# DATALOGGER_CA_ADC_V1.net
KiCad netlist of a schematic drawn in EAGLE
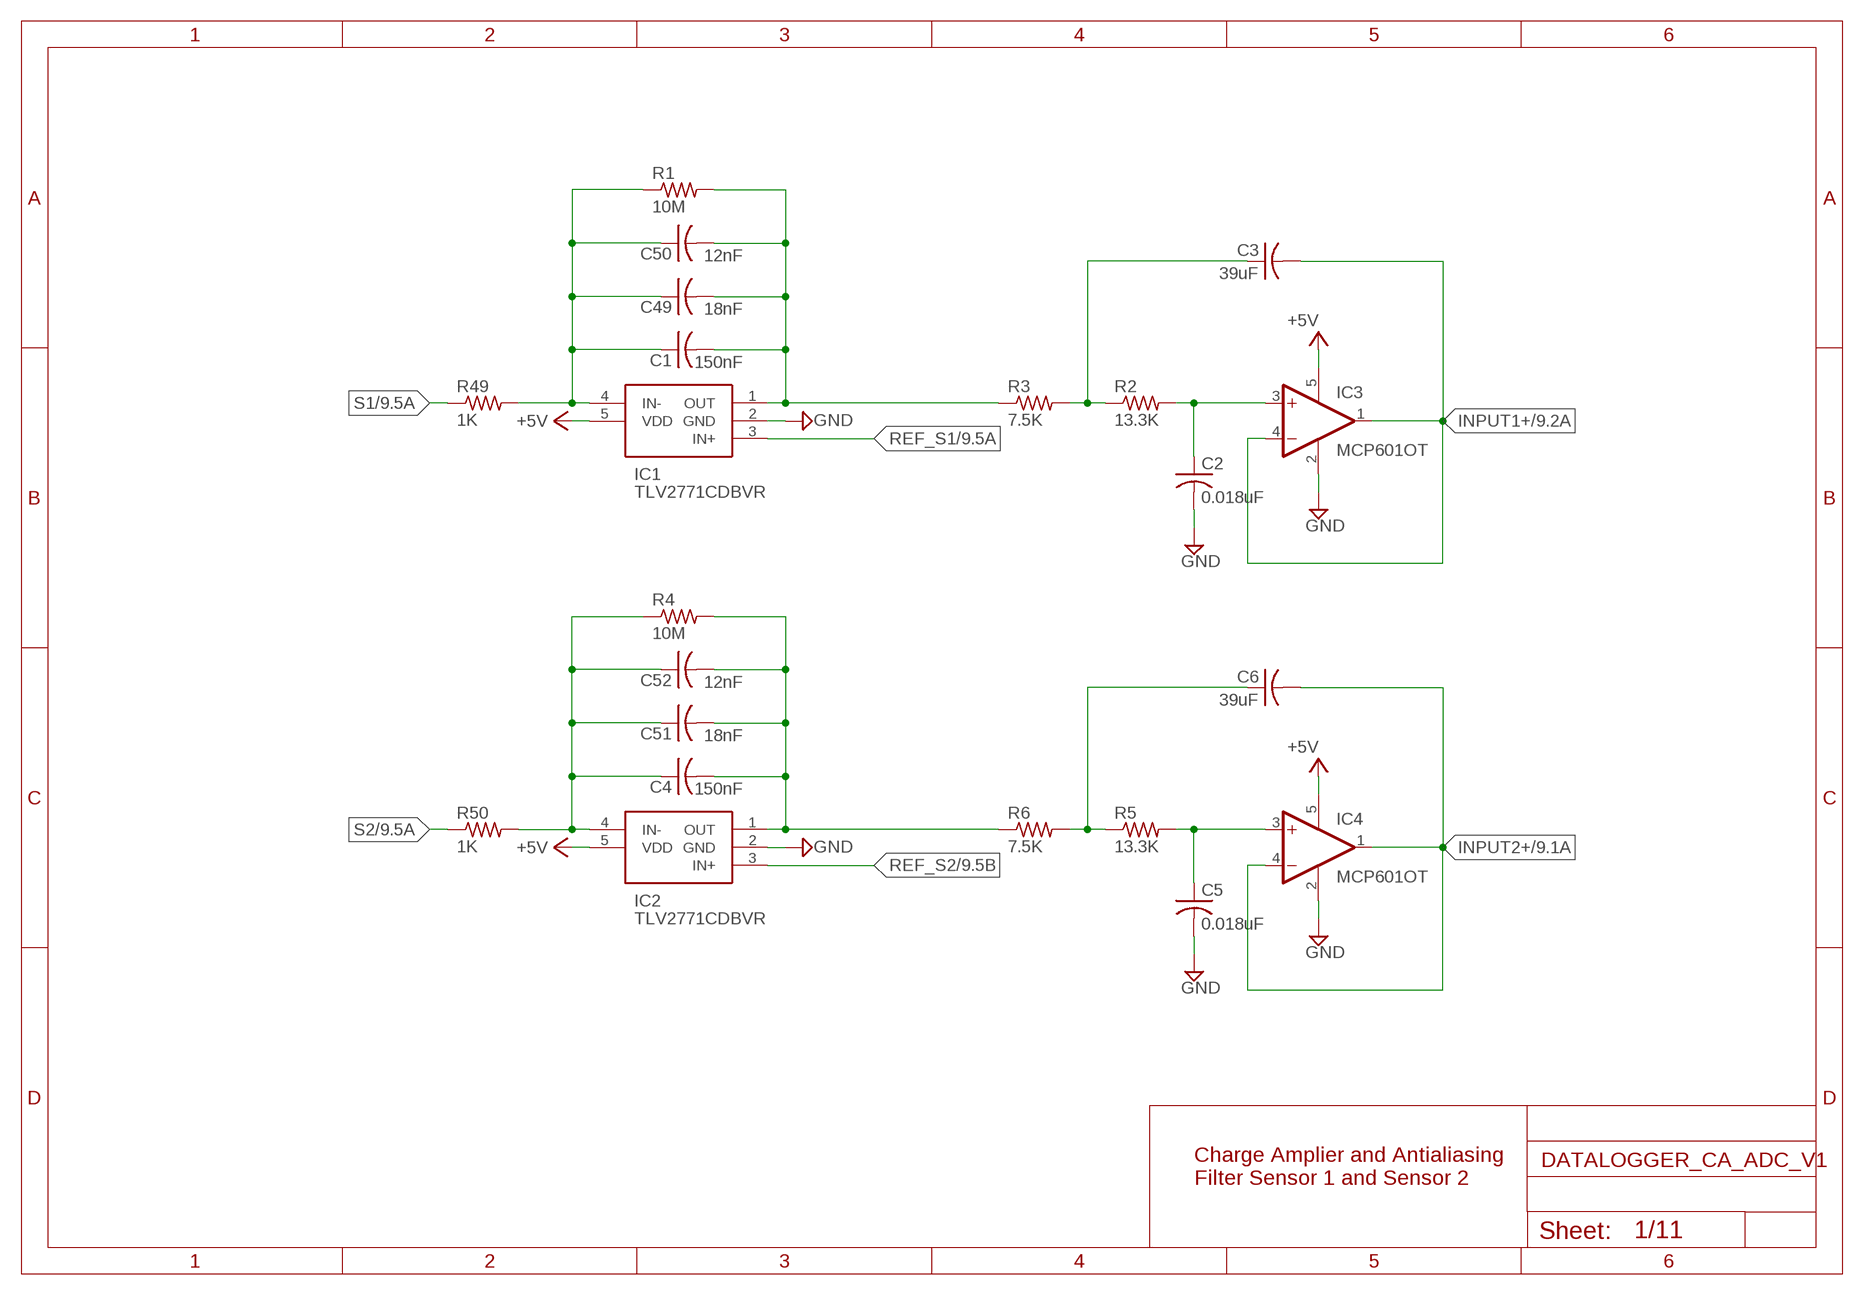
[diagram p0: schematic, sheet 1]
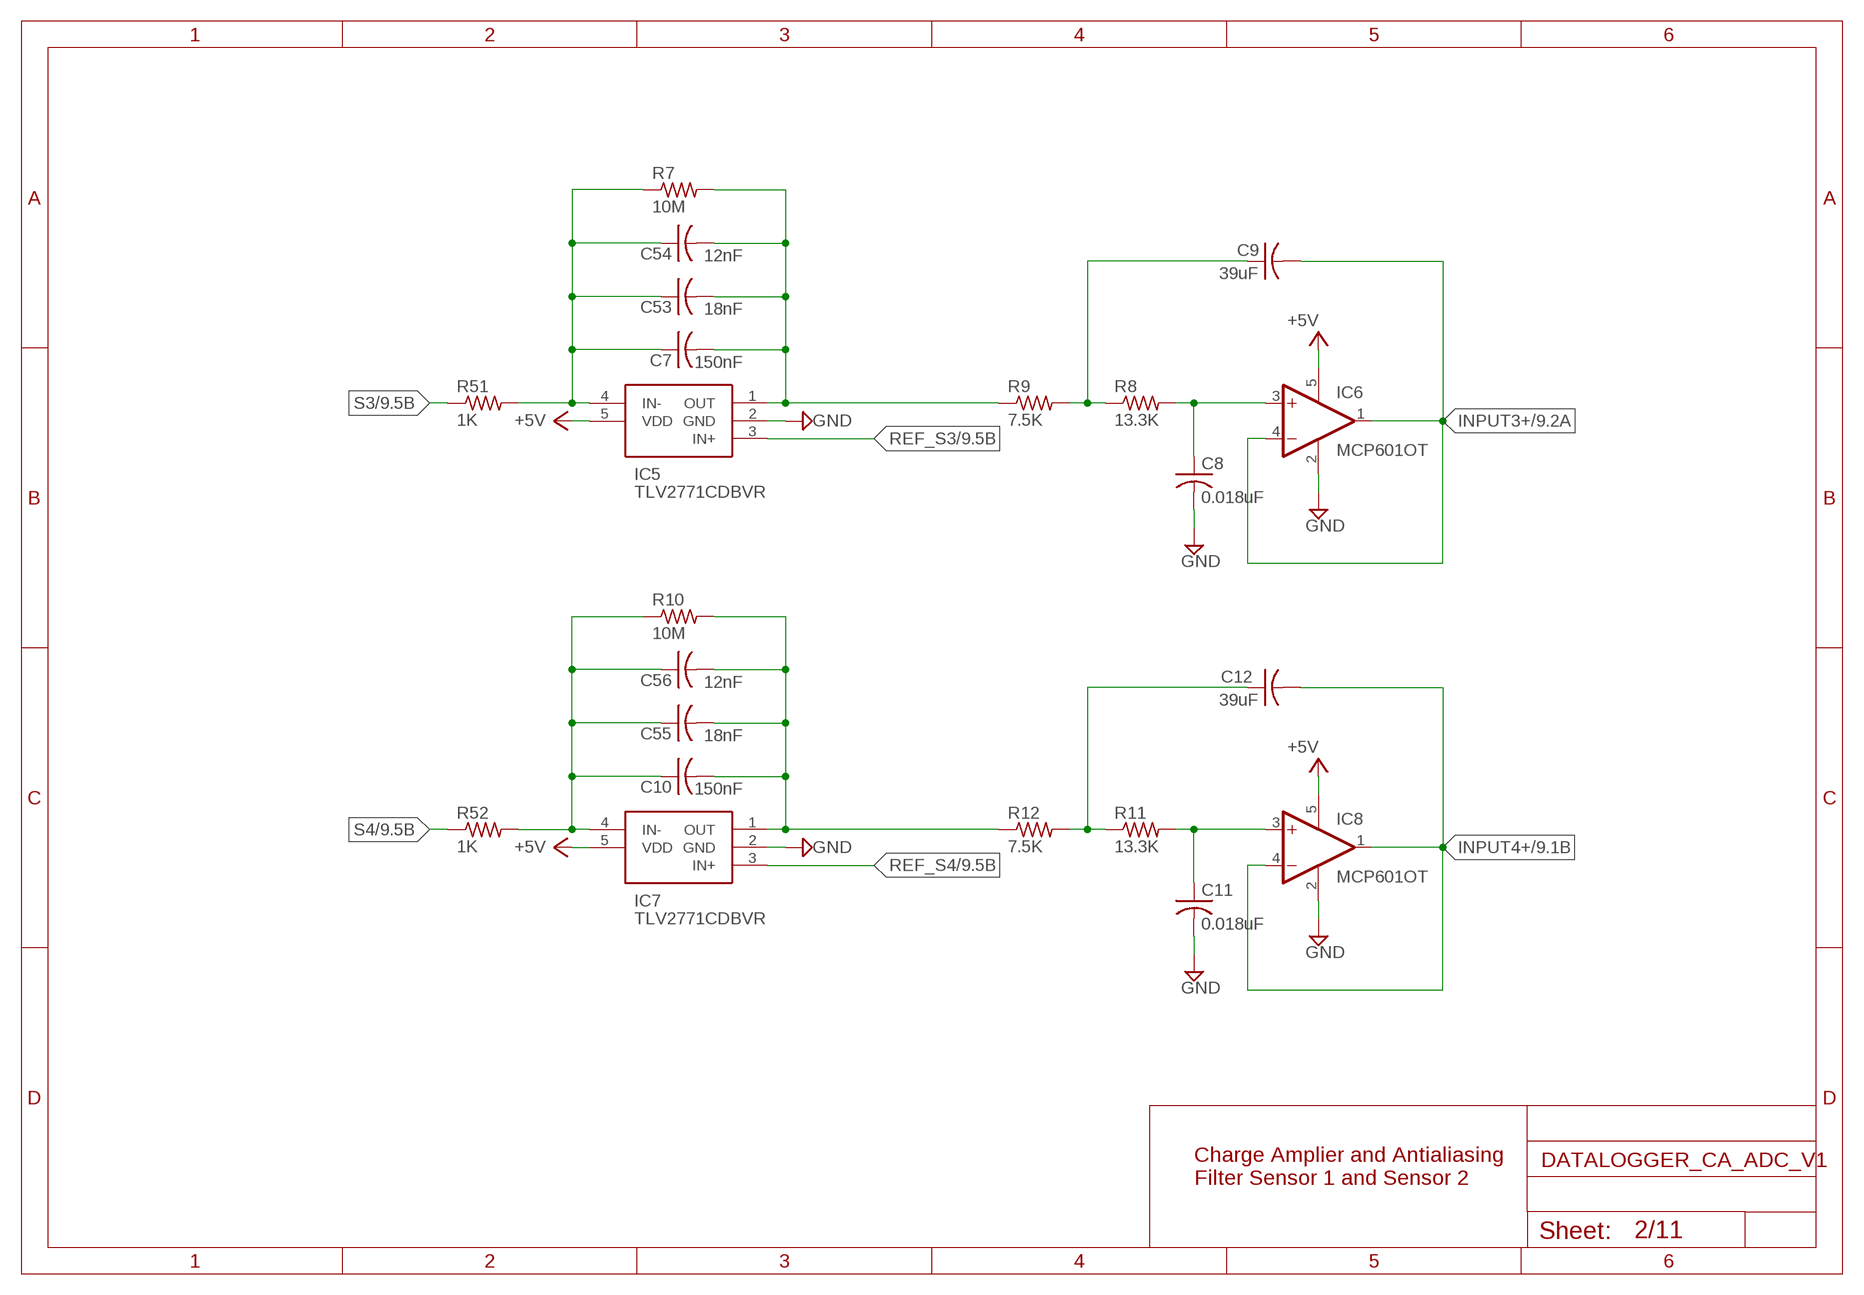
[diagram p1: schematic, sheet 2]
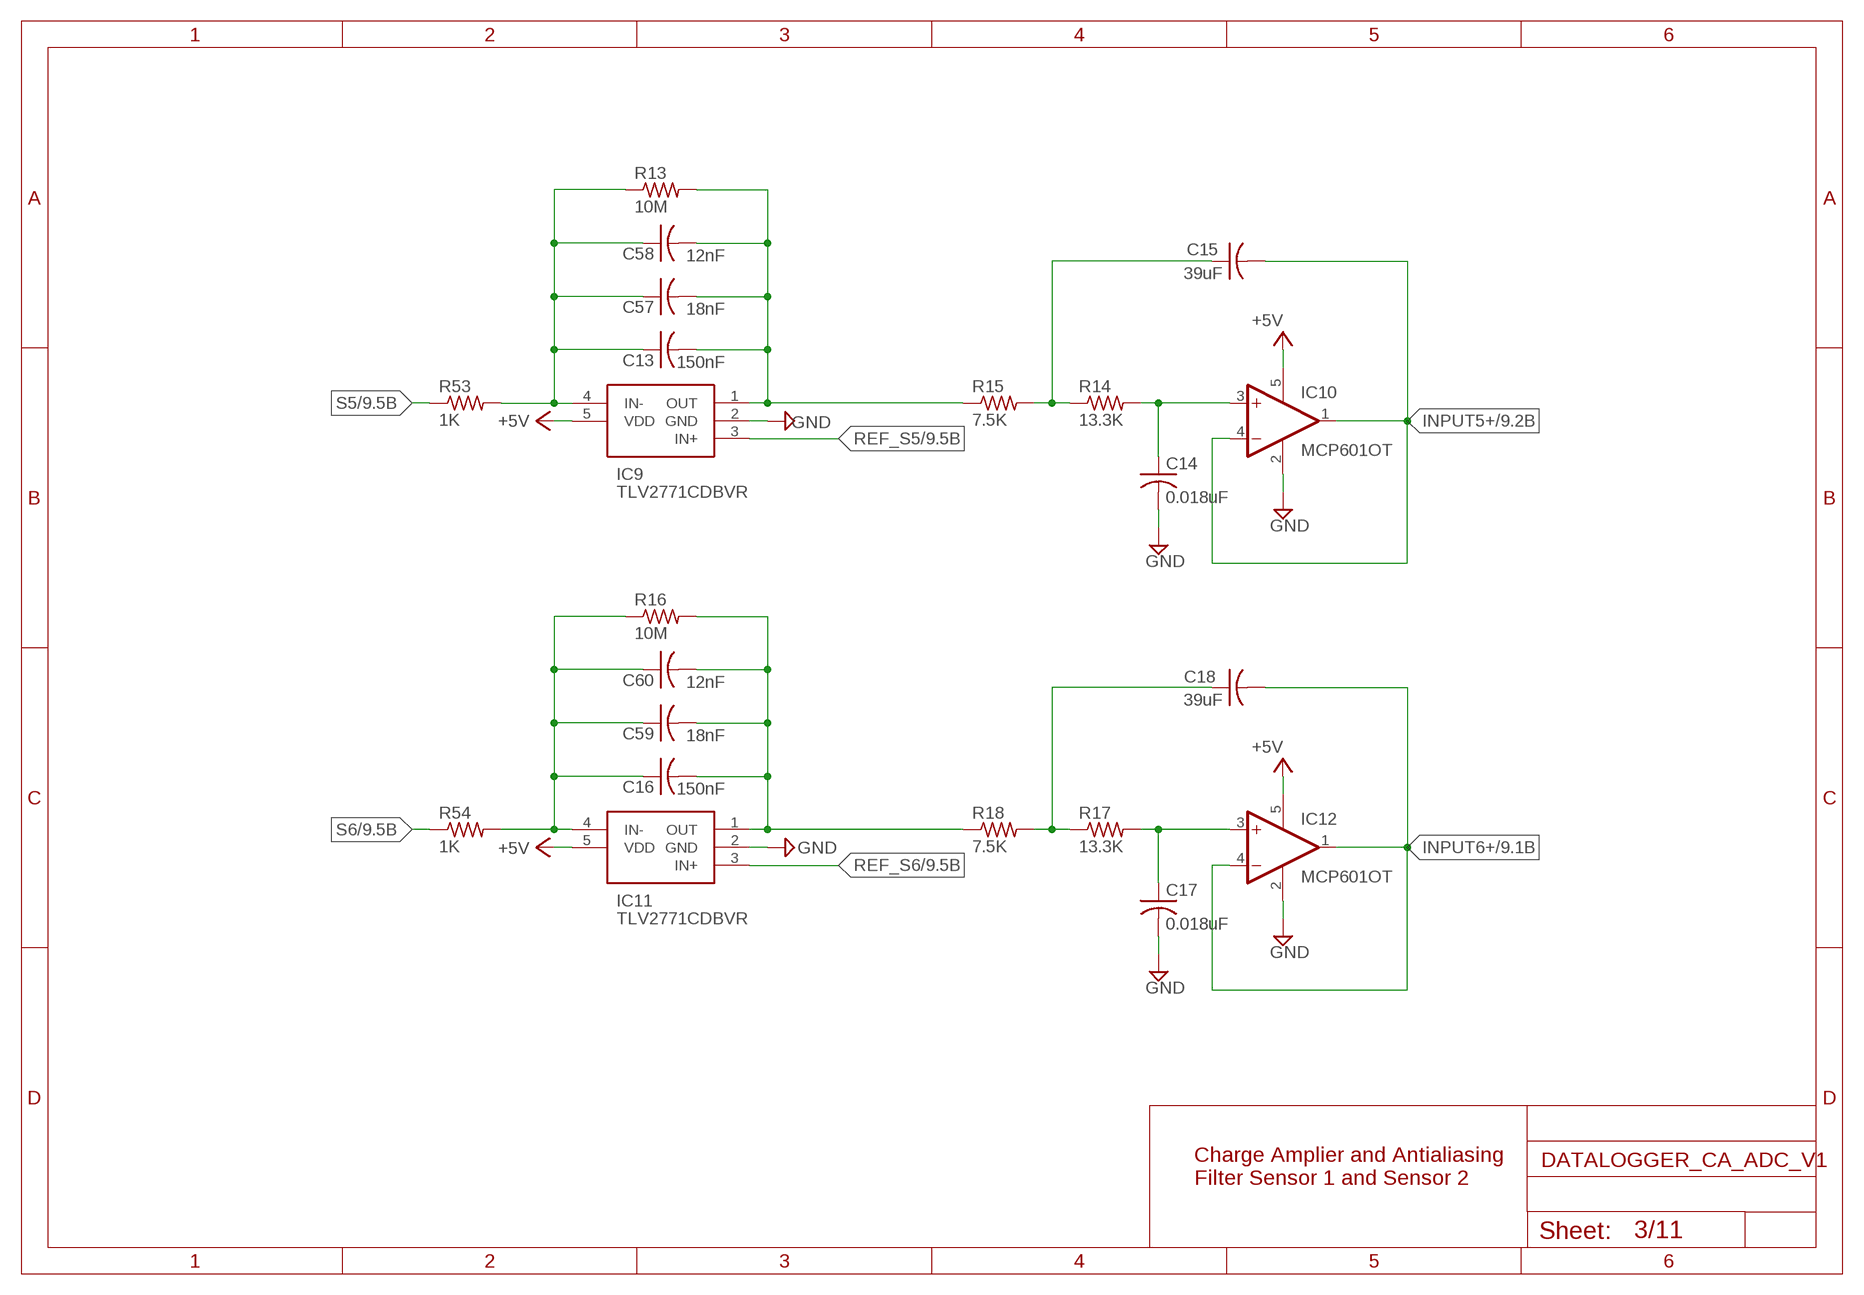
[diagram p2: schematic, sheet 3]
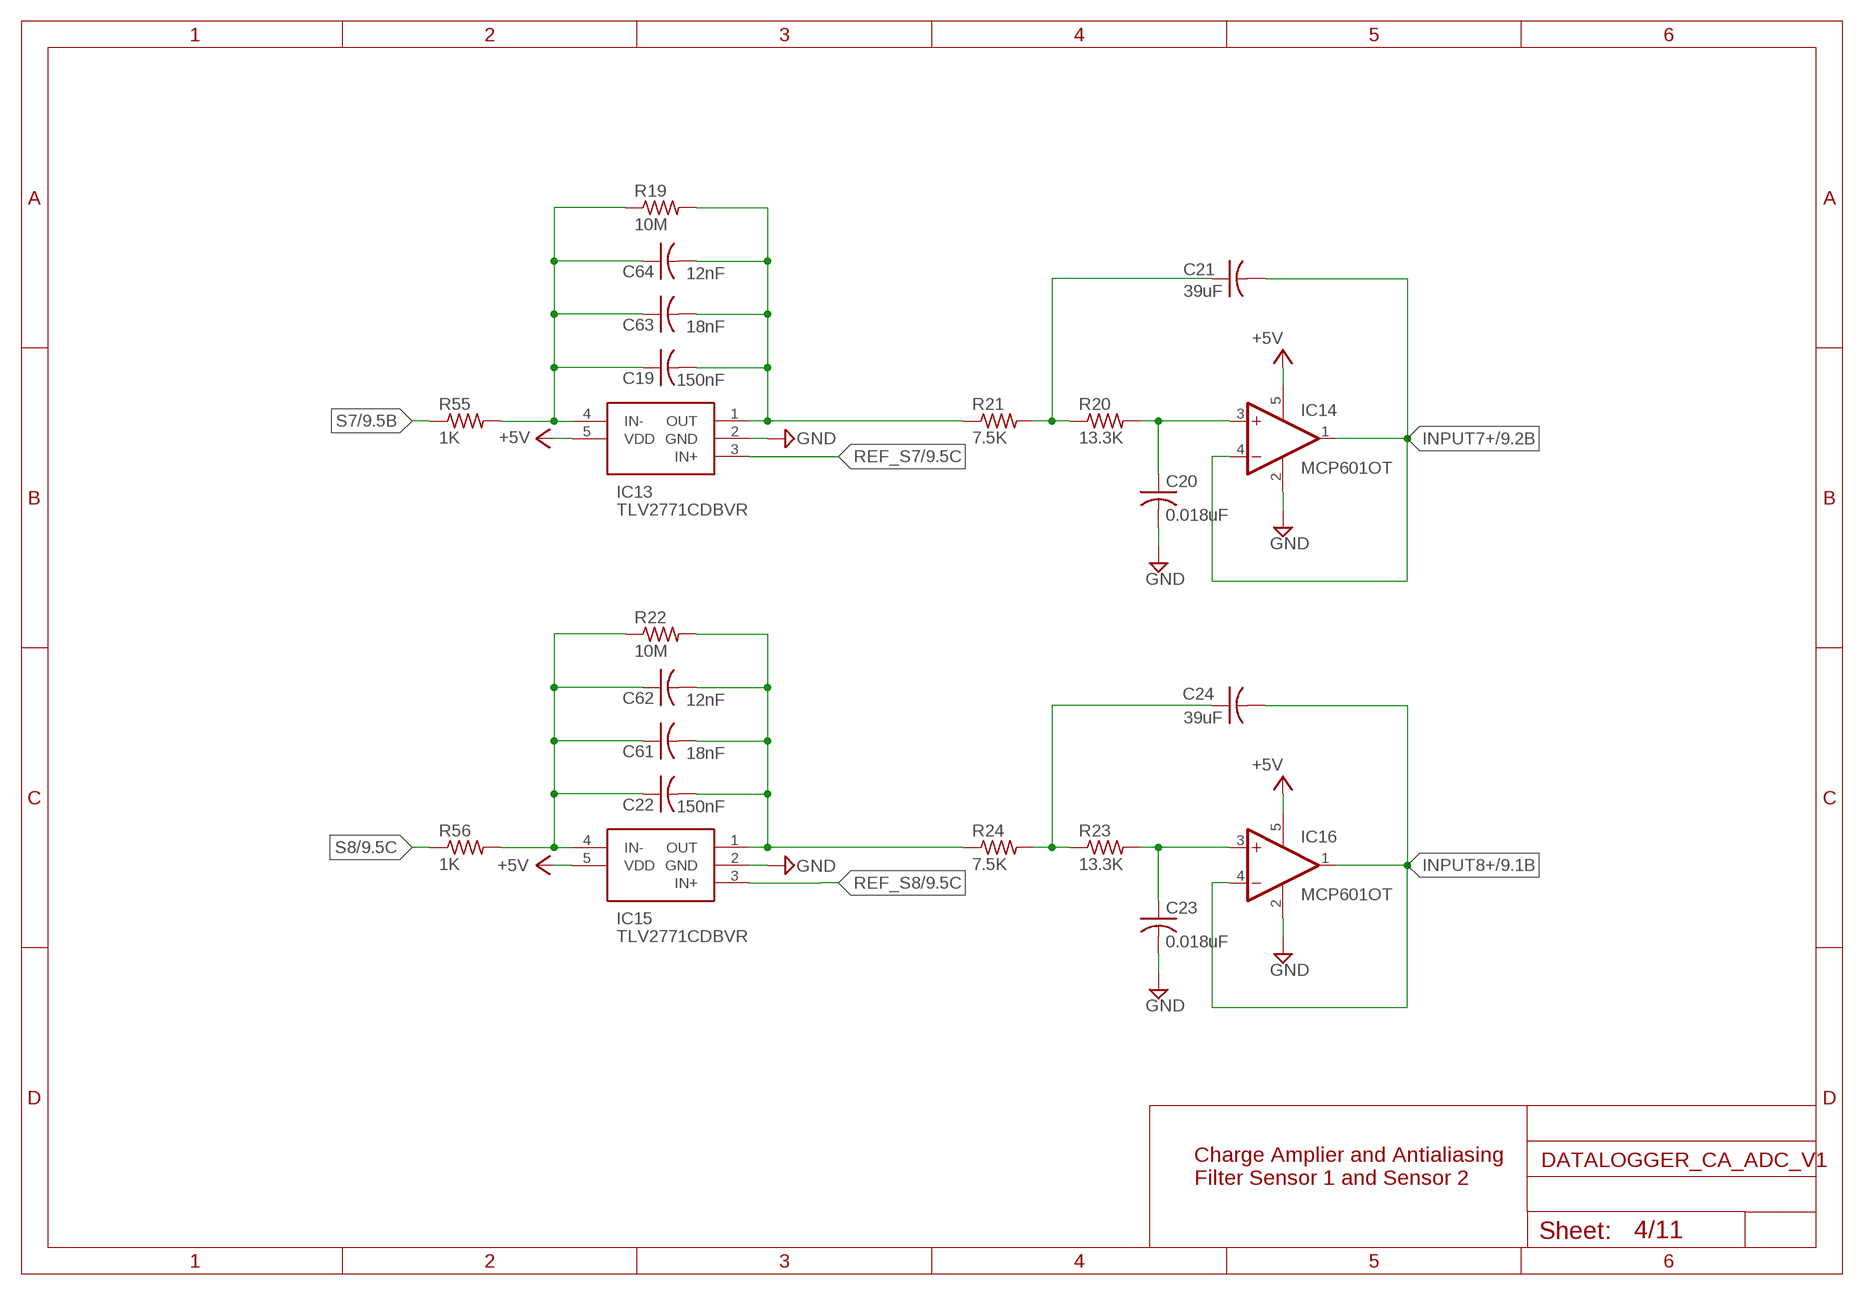
[diagram p3: schematic, sheet 4]
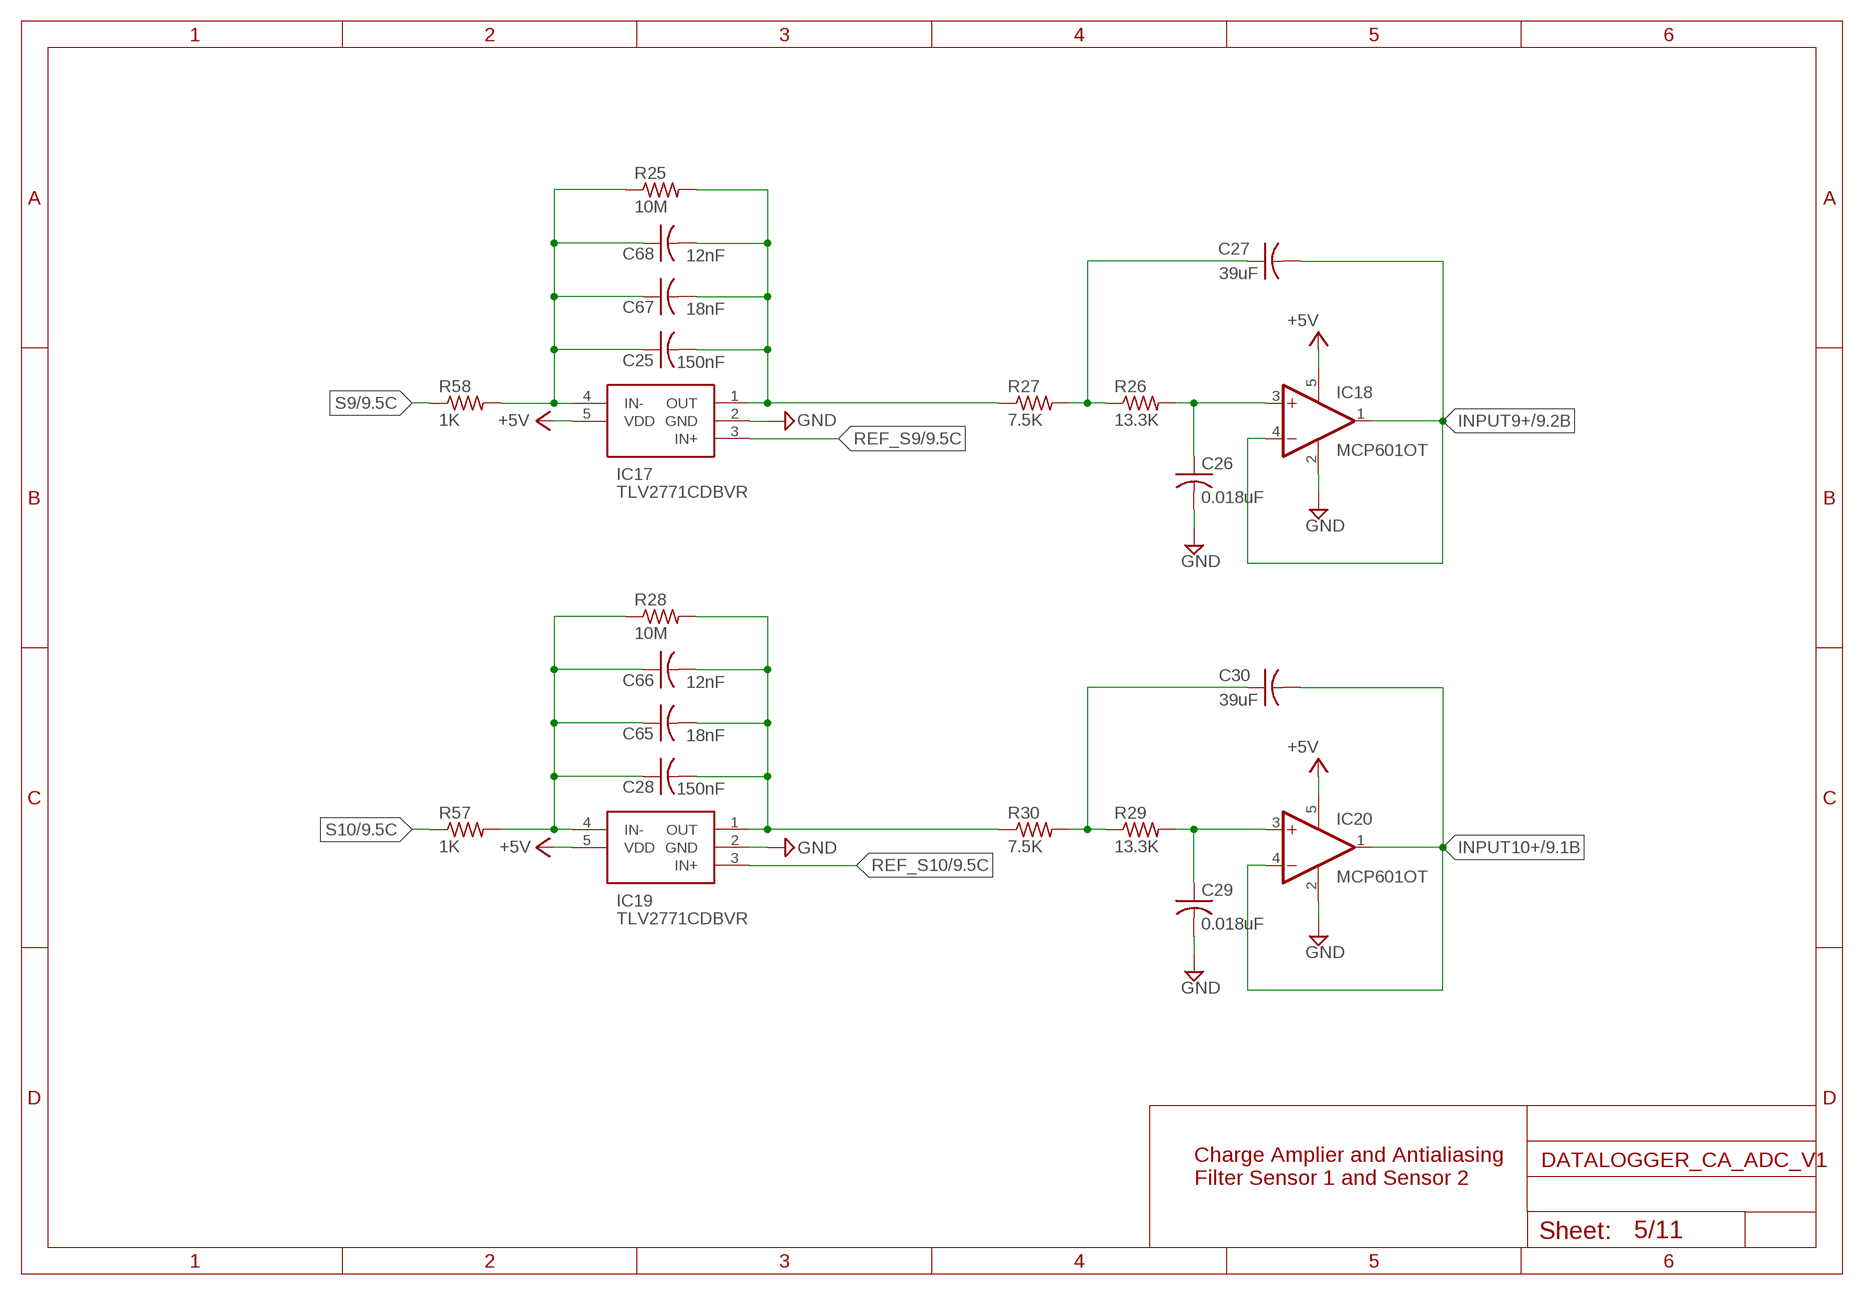
[diagram p4: schematic, sheet 5]
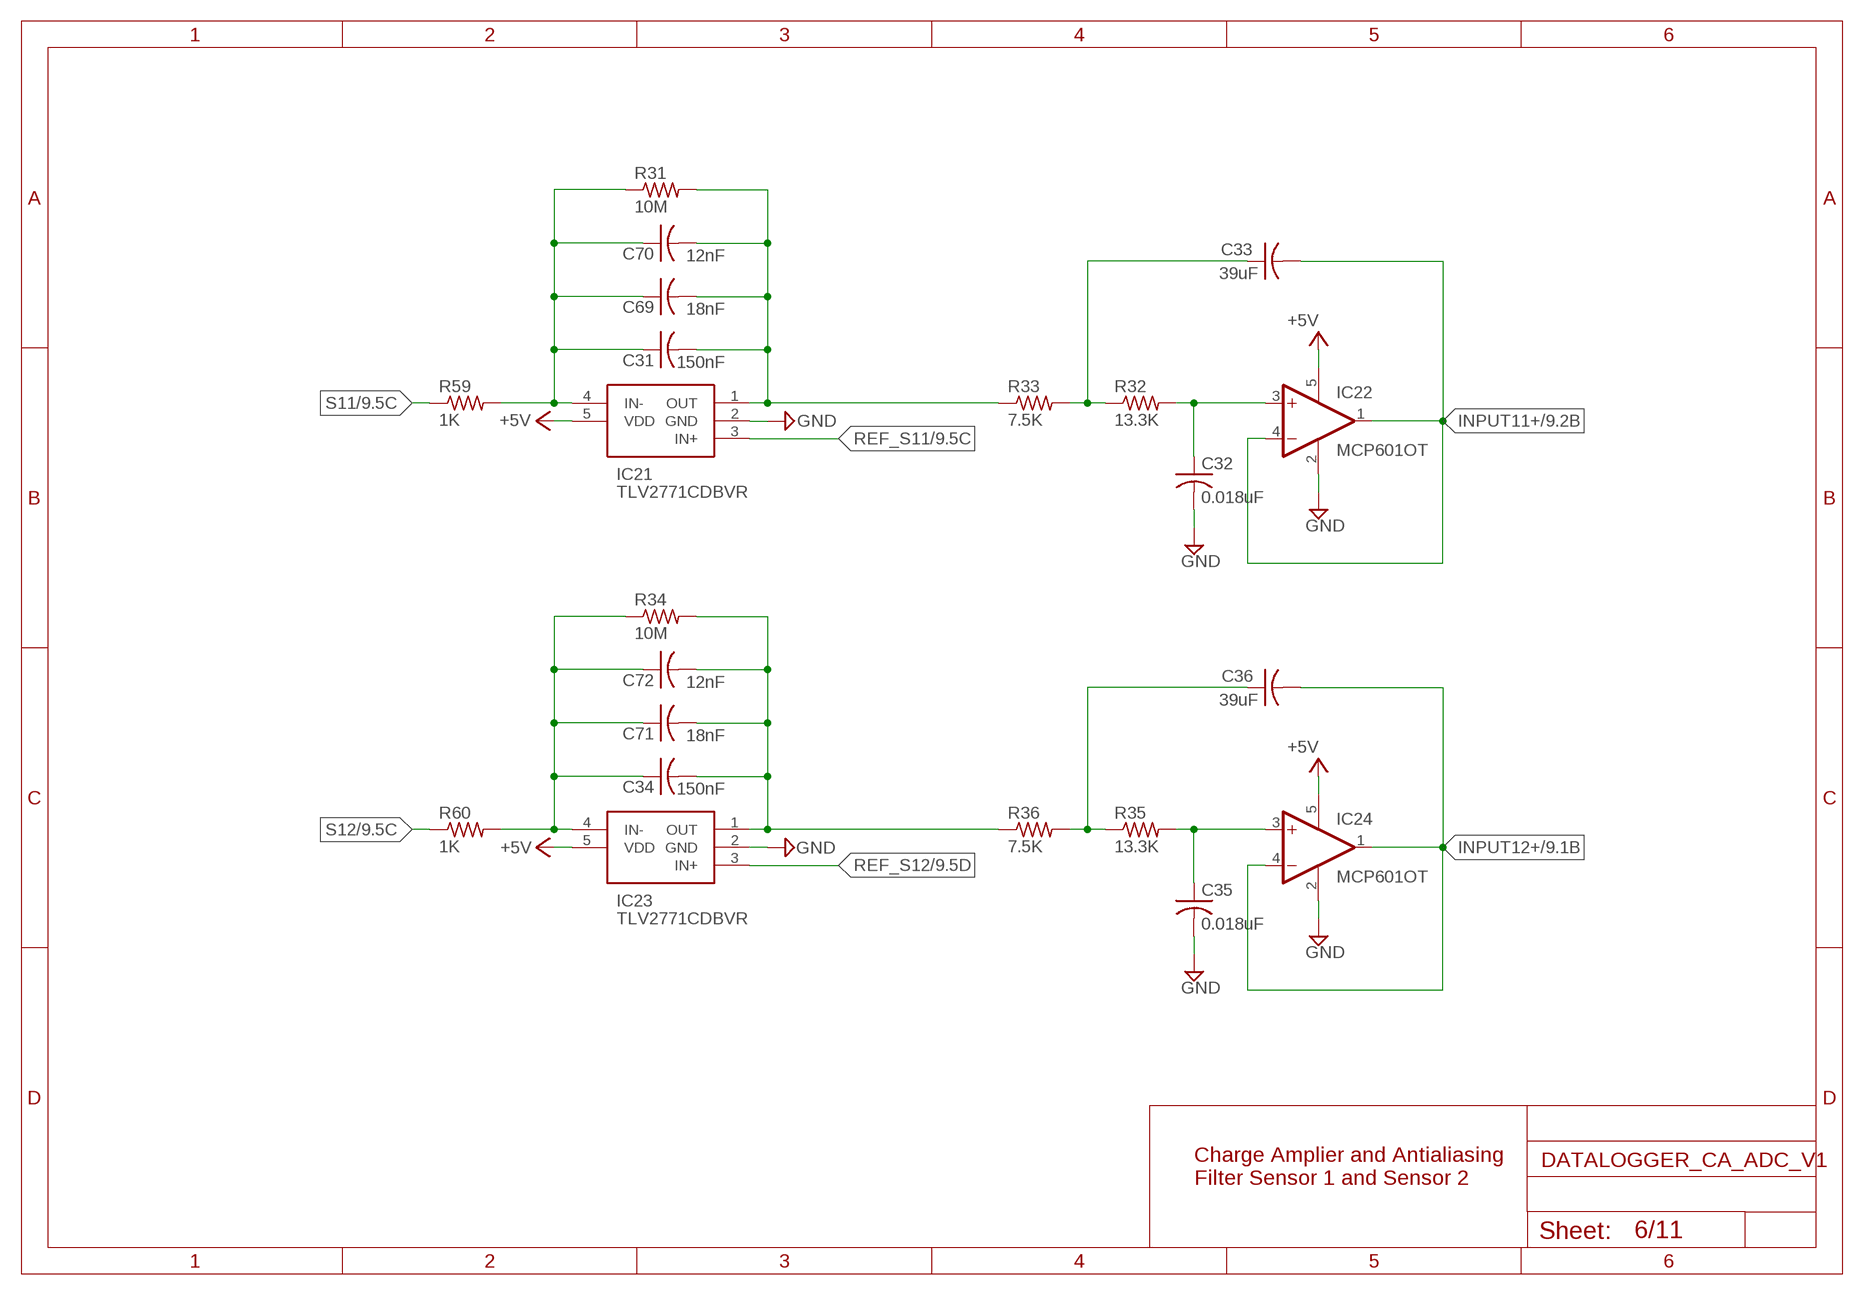
[diagram p5: schematic, sheet 6]
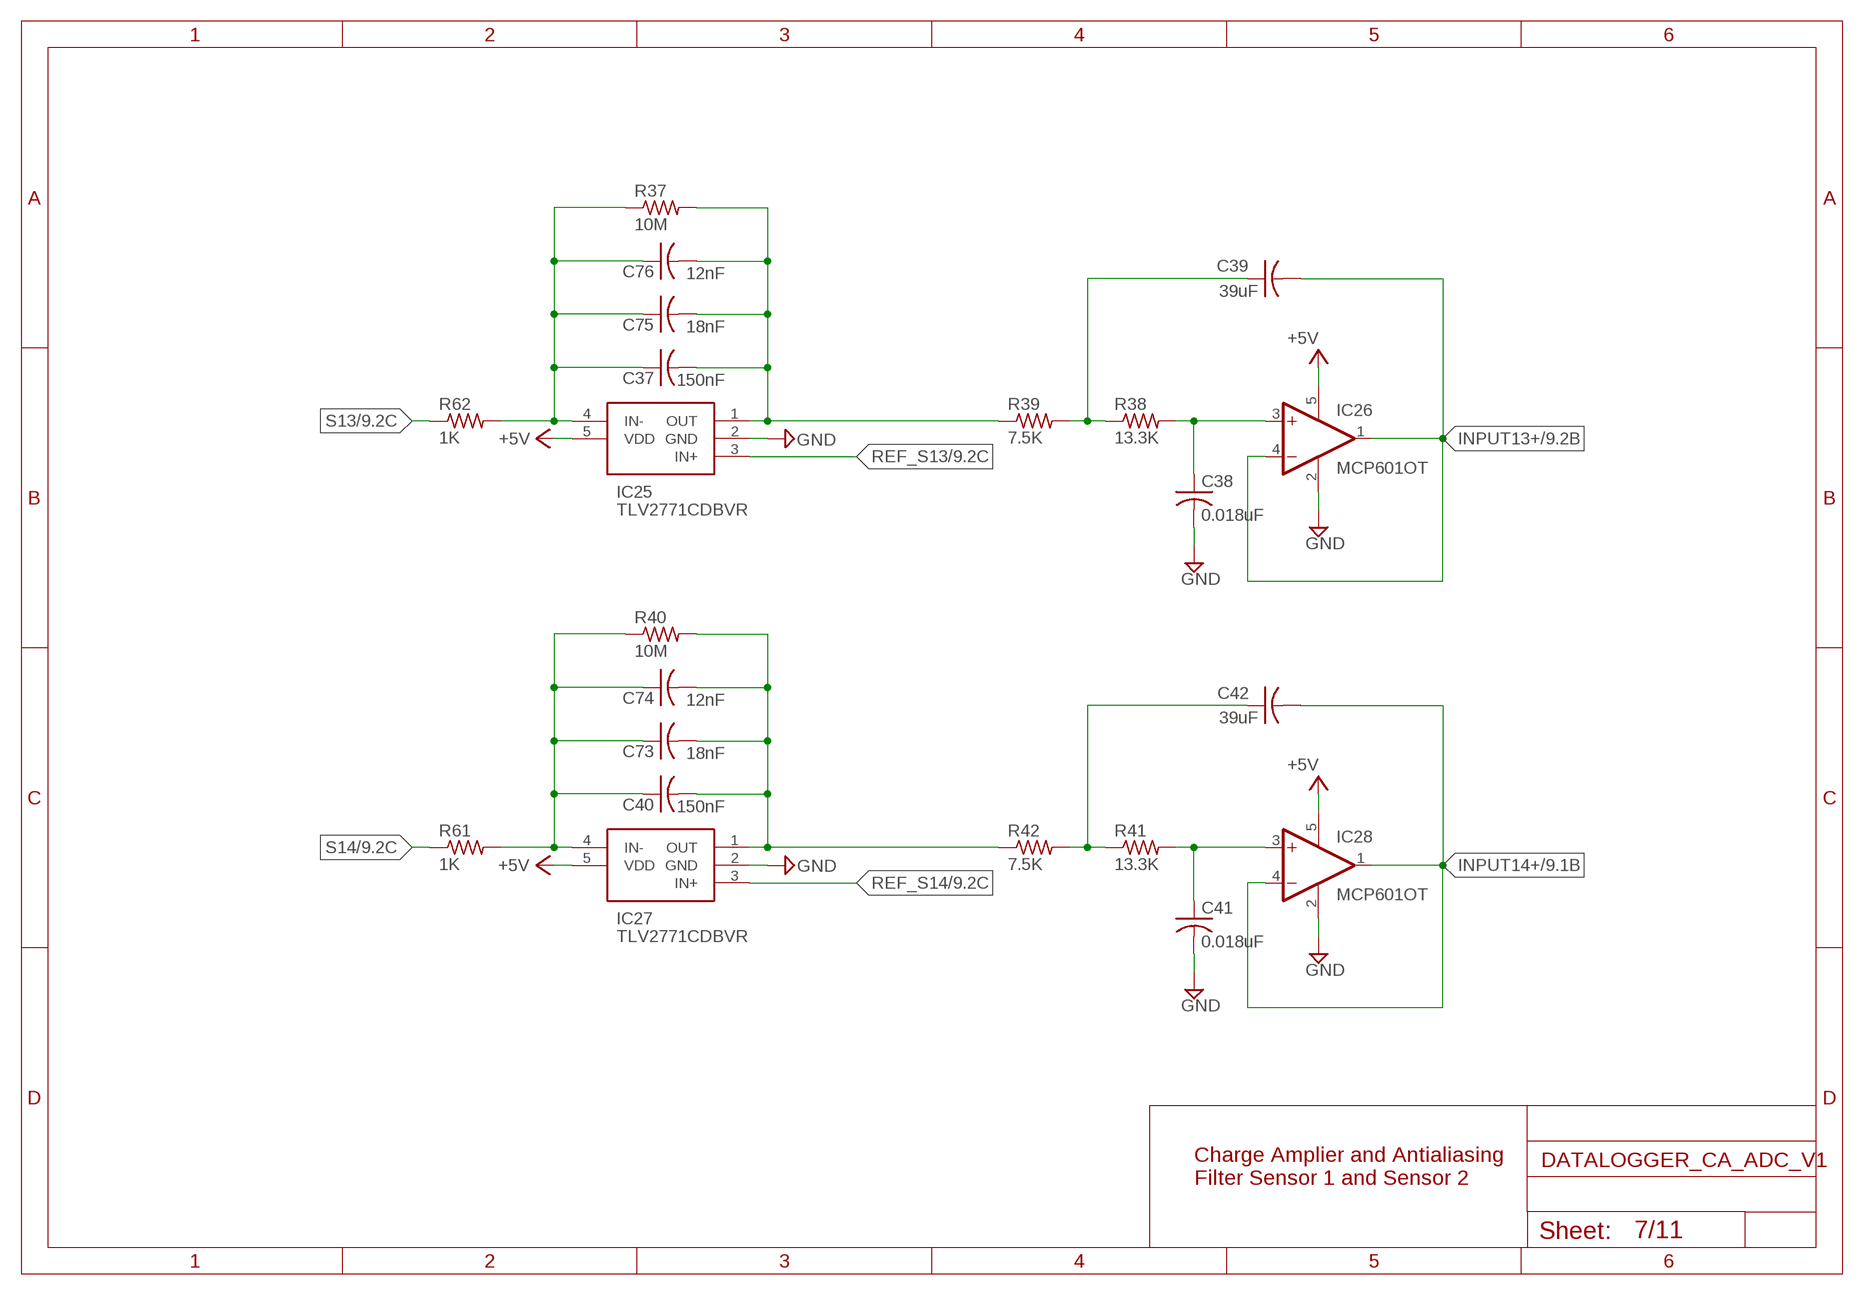
[diagram p6: schematic, sheet 7]
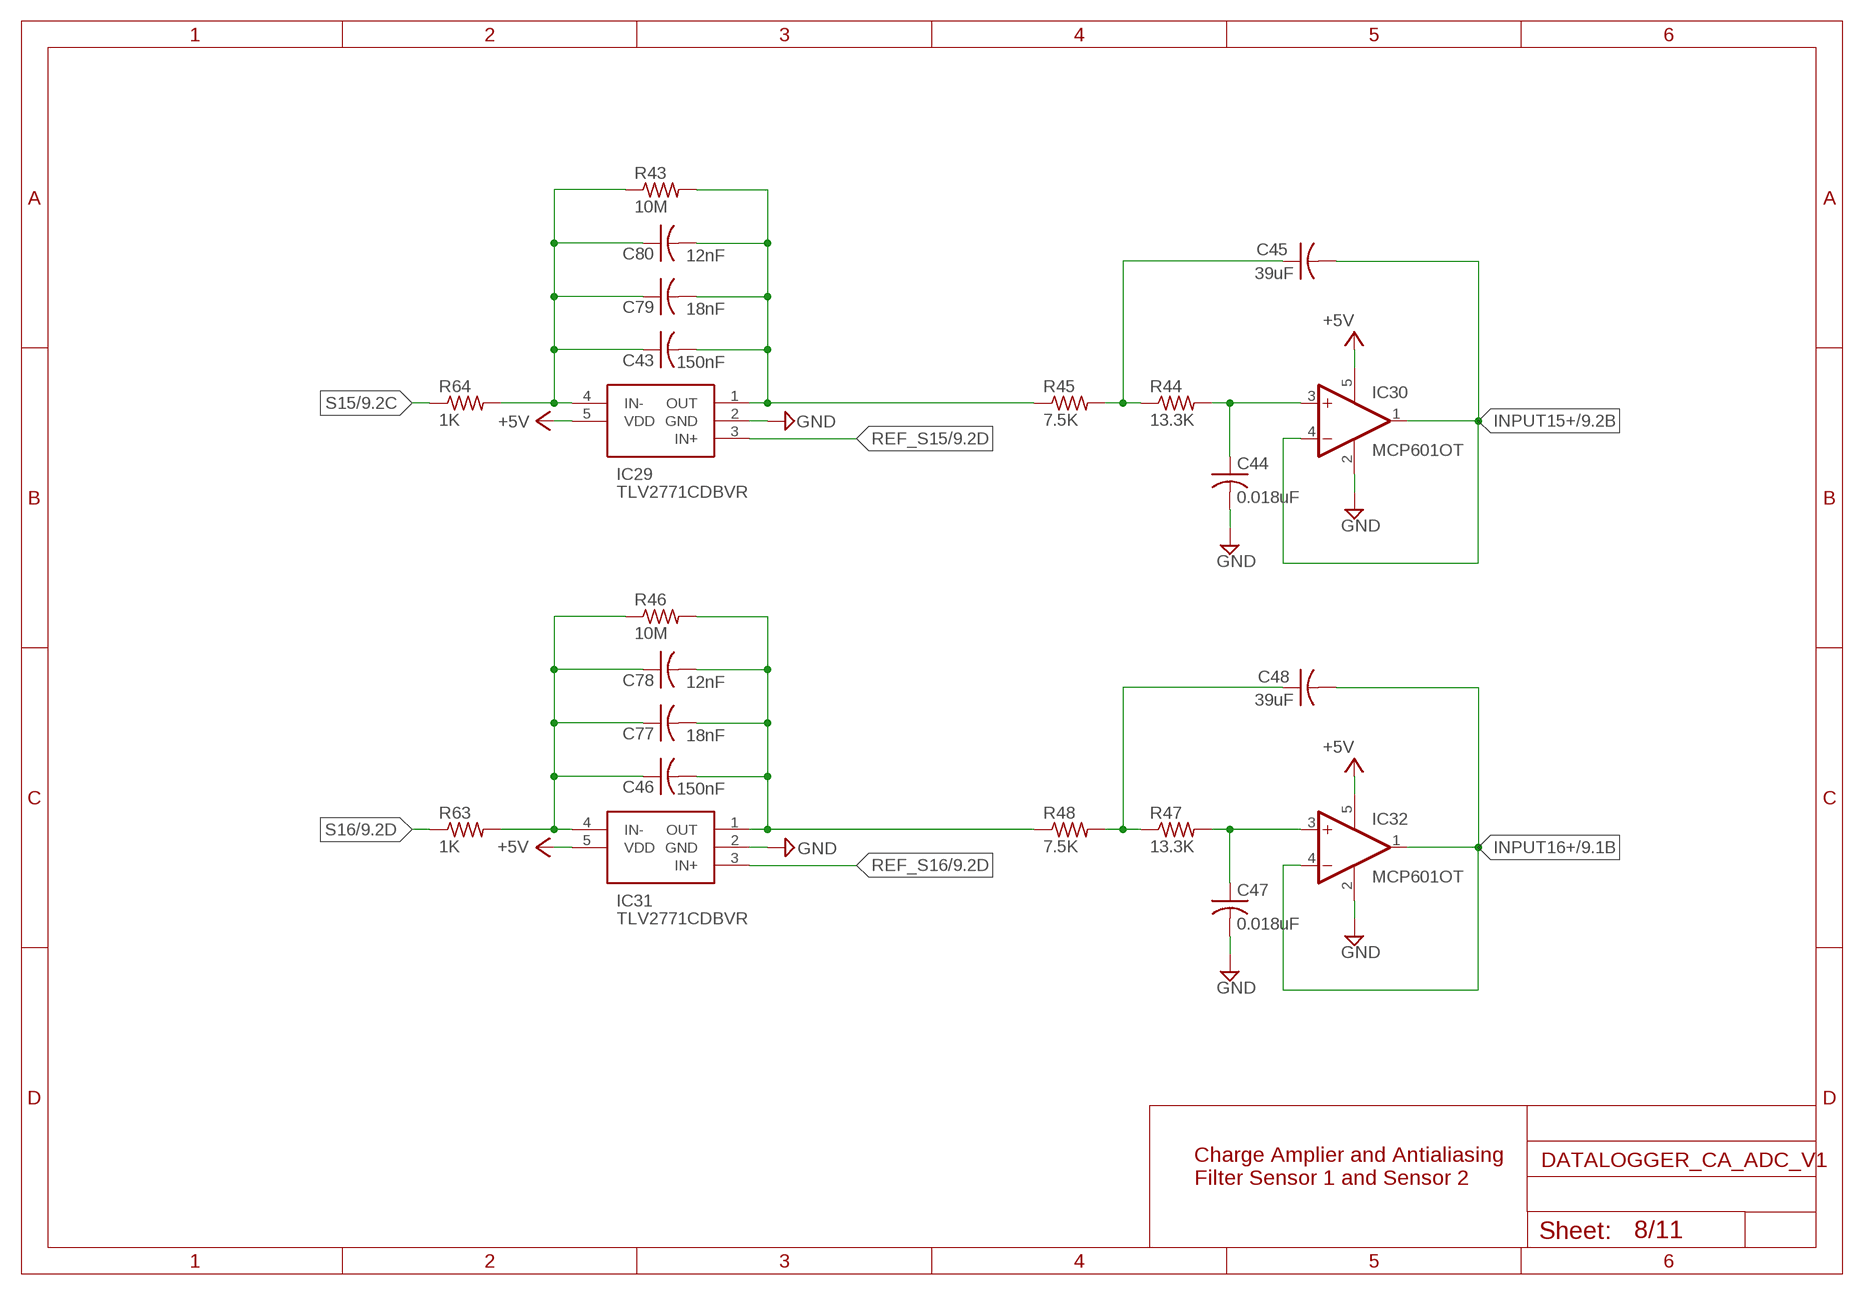
[diagram p7: schematic, sheet 8]
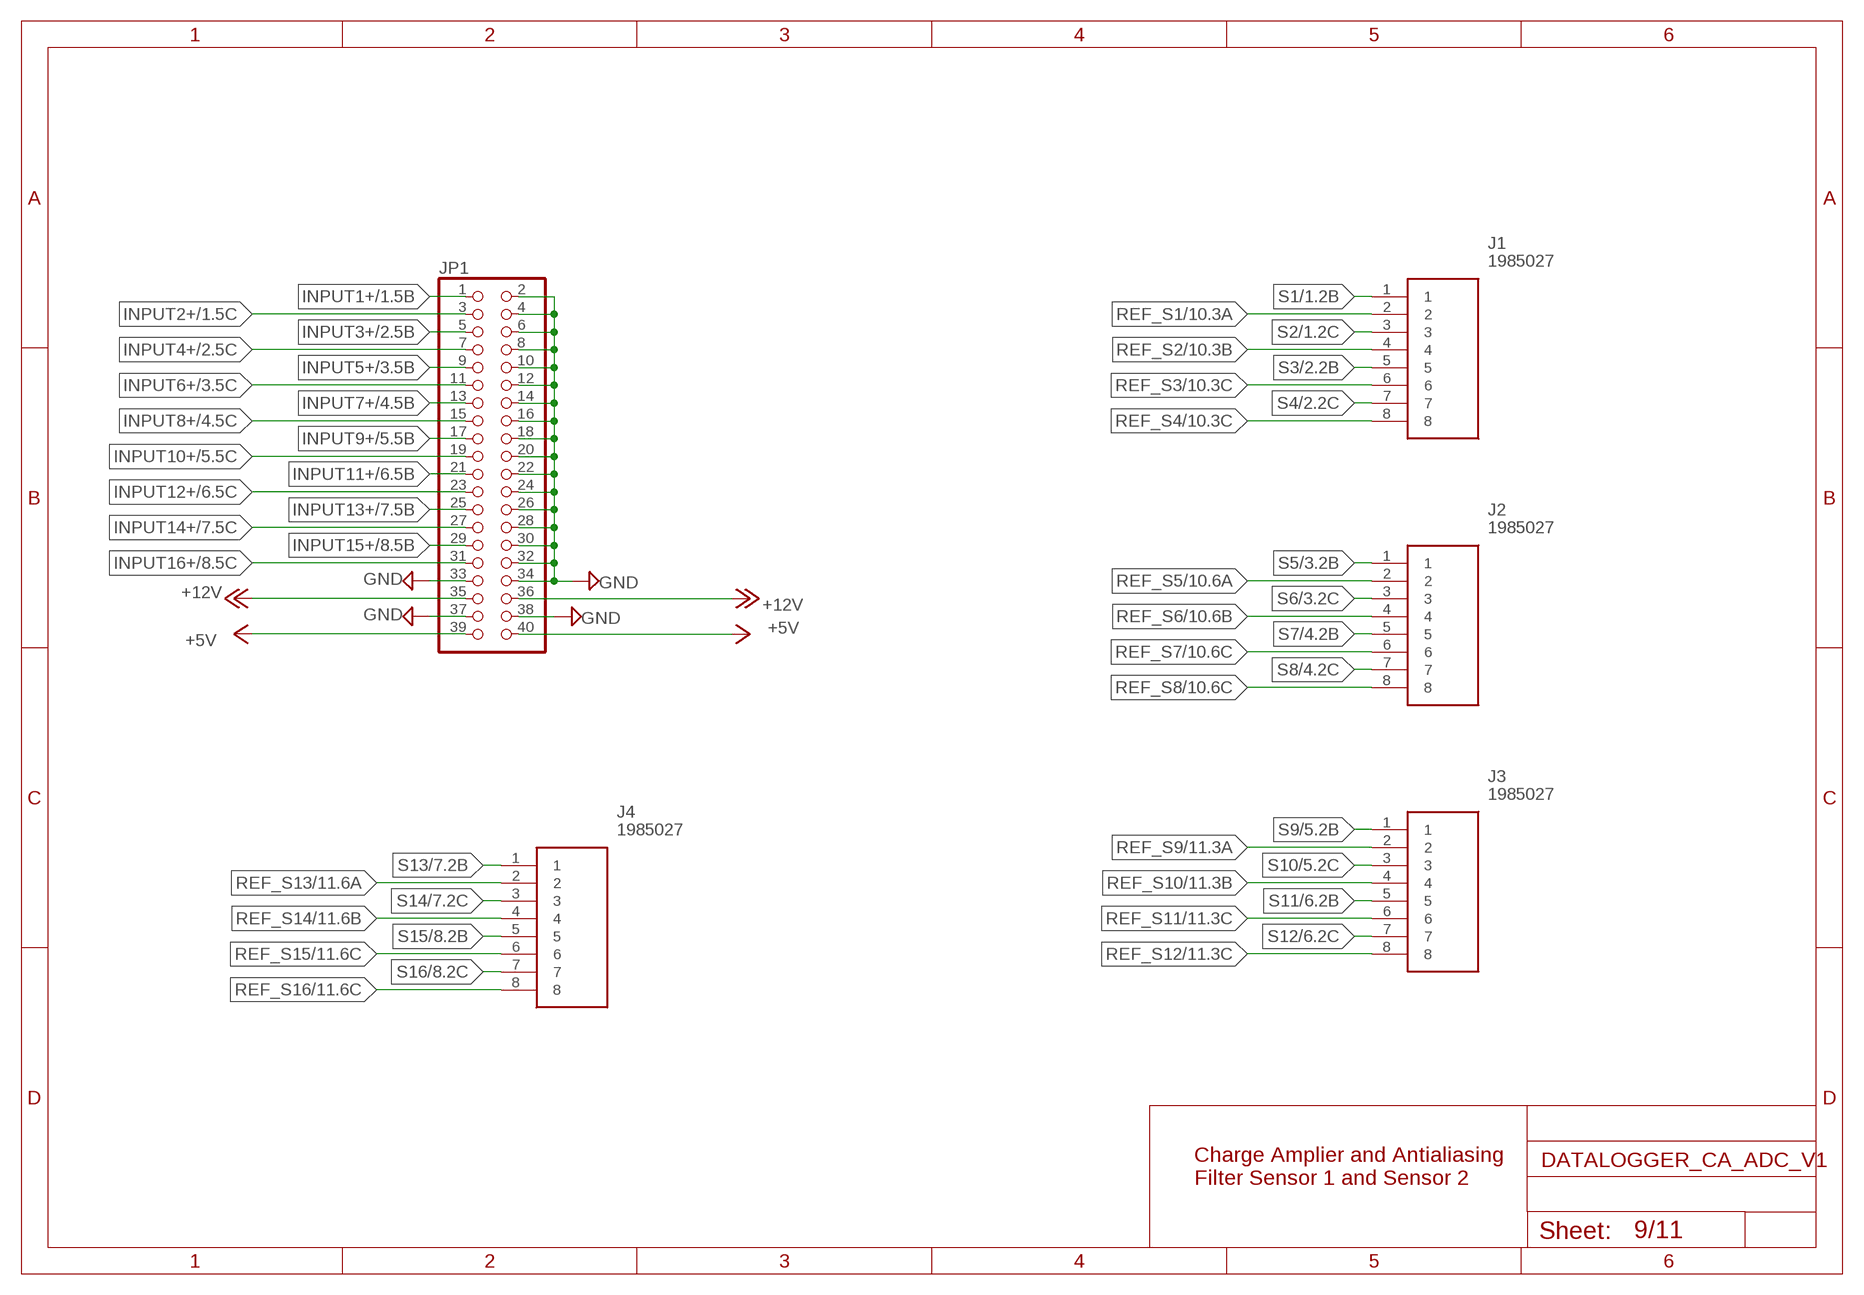
[diagram p8: schematic, sheet 9]
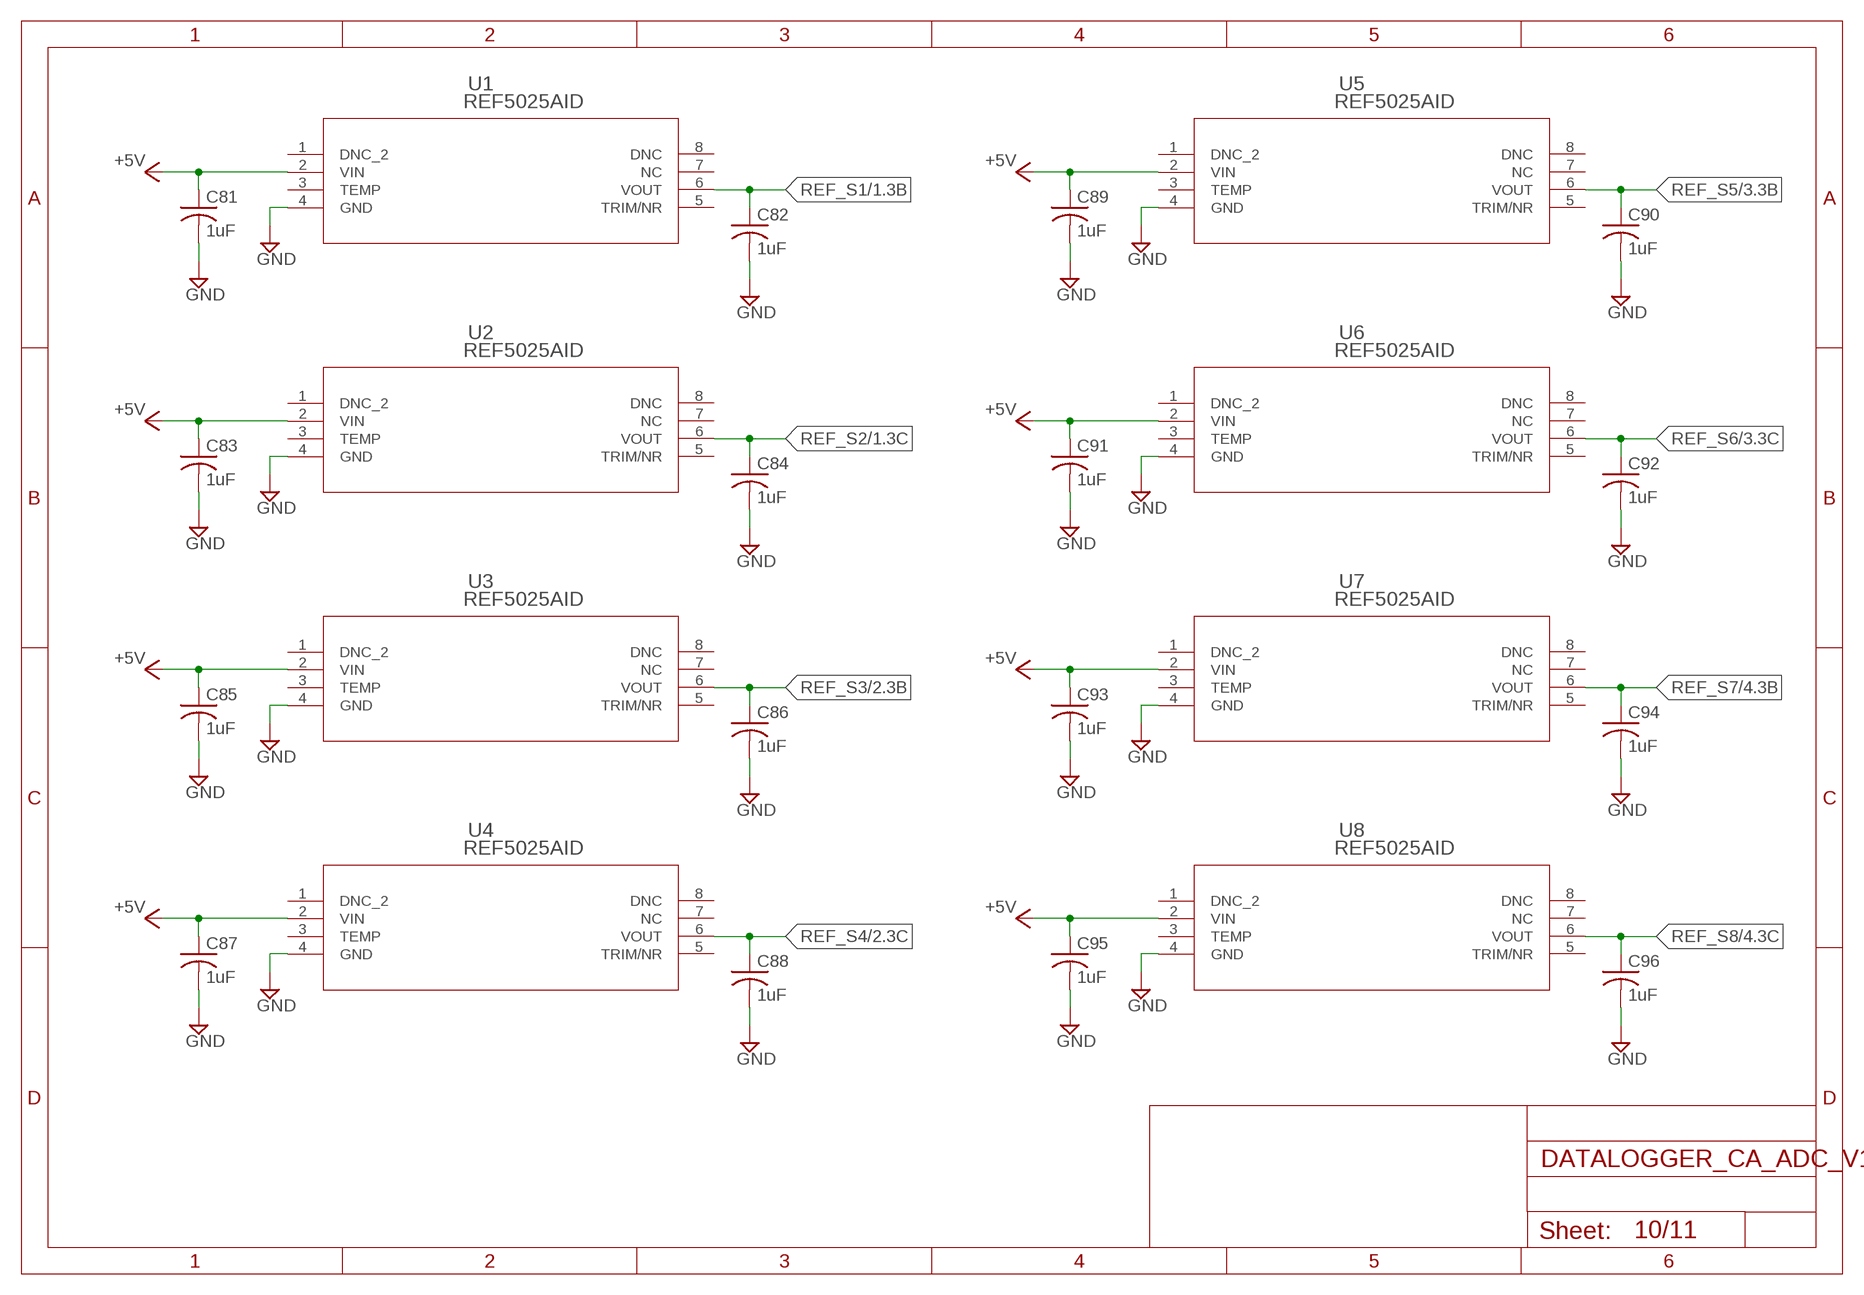
[diagram p9: schematic, sheet 10]
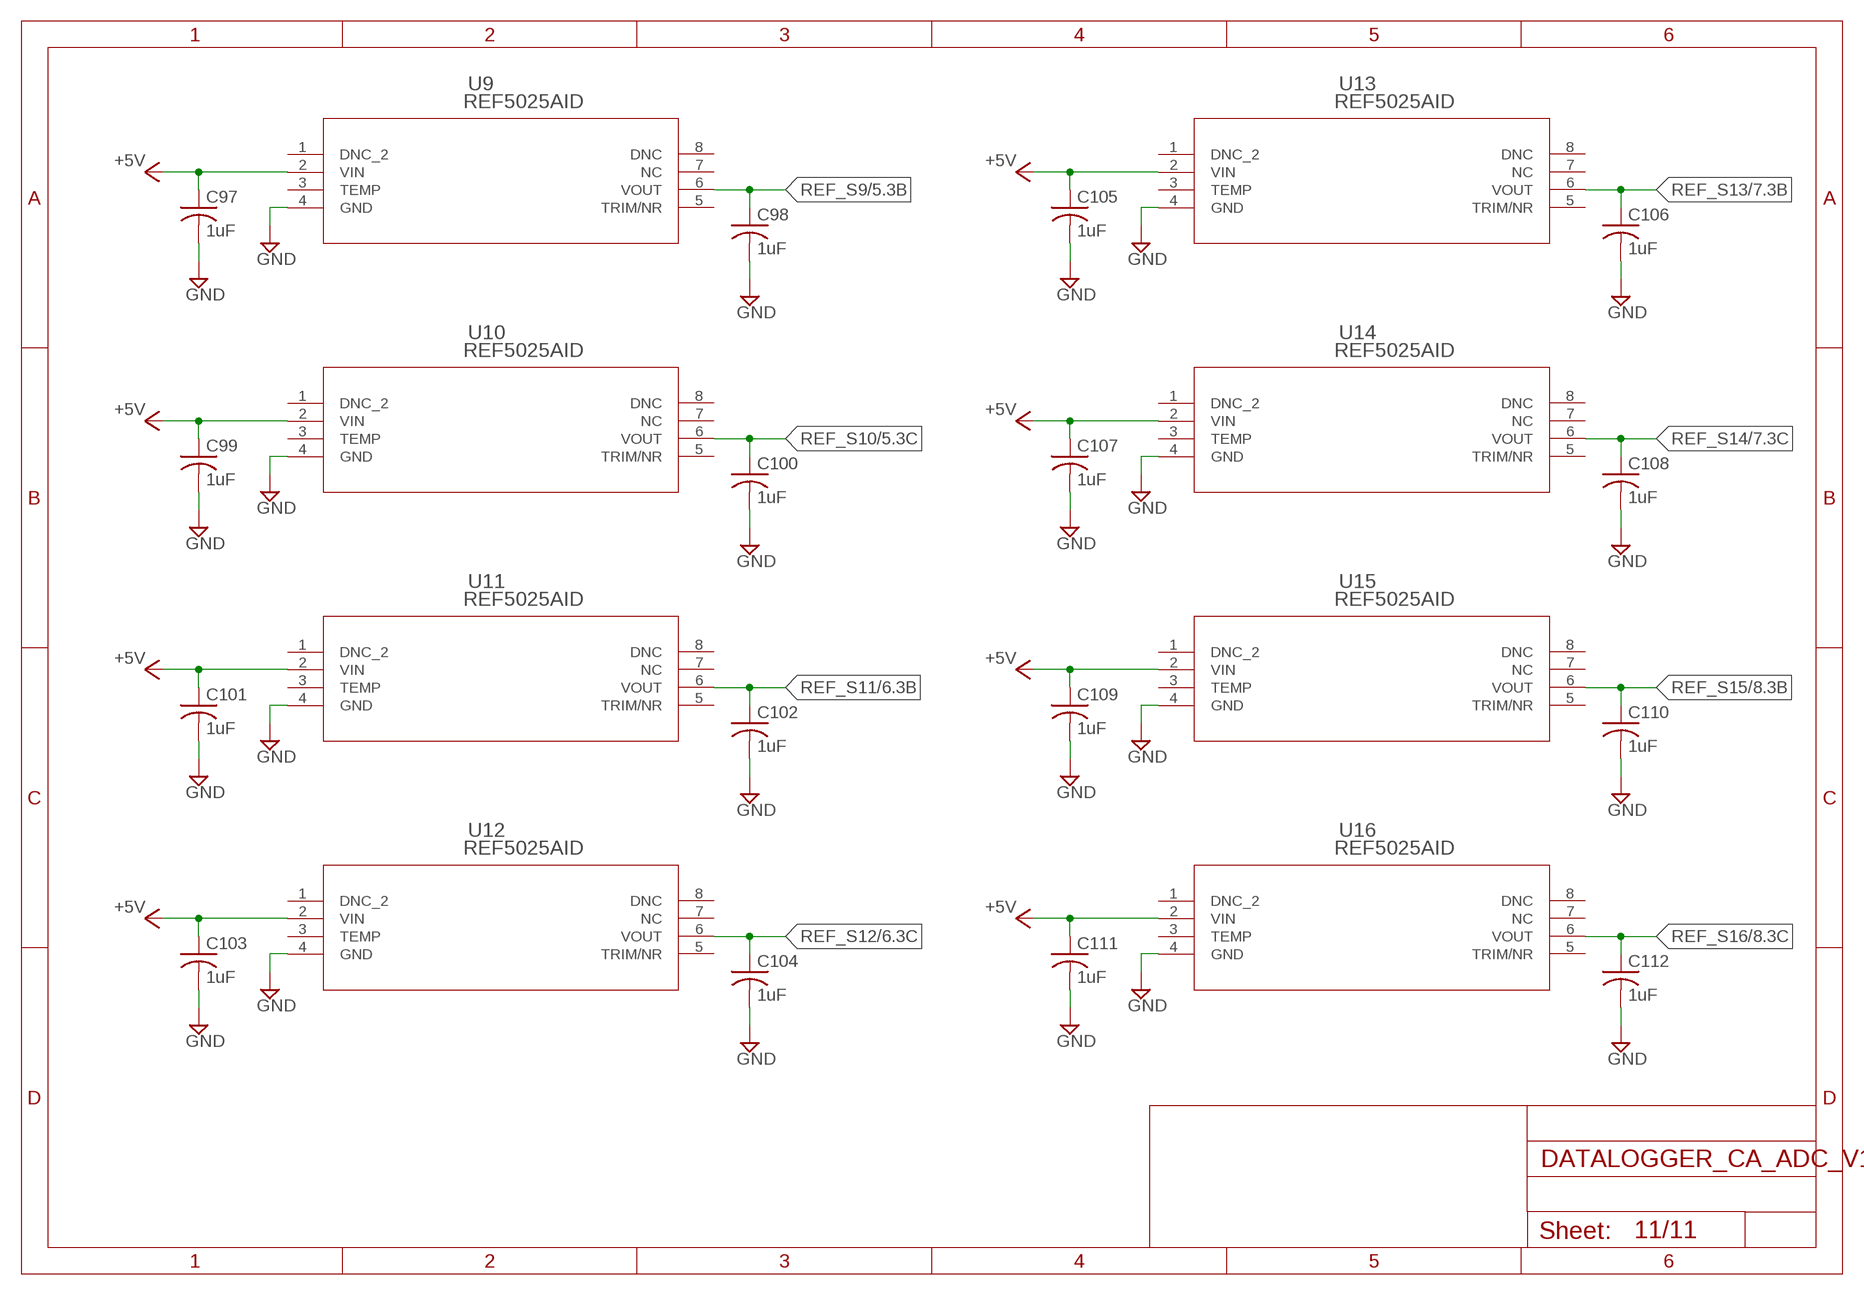
[diagram p10: schematic, sheet 11]

(export (version "E")
  (design (tool "Eeschema 10.0.6"))
  (components
    (comp (ref "C13")
      (value "150nF")
      (footprint "eagle-import:C0805")
      (libsource (lib "eagle-import") (part "C-USC0805"))
    )
    (comp (ref "C14")
      (value "0.018uF")
      (footprint "eagle-import:C0805")
      (libsource (lib "eagle-import") (part "C-USC0805"))
    )
    (comp (ref "C15")
      (value "39uF")
      (footprint "eagle-import:C0805")
      (libsource (lib "eagle-import") (part "C-USC0805"))
    )
    (comp (ref "C16")
      (value "150nF")
      (footprint "eagle-import:C0805")
      (libsource (lib "eagle-import") (part "C-USC0805"))
    )
    (comp (ref "C17")
      (value "0.018uF")
      (footprint "eagle-import:C0805")
      (libsource (lib "eagle-import") (part "C-USC0805"))
    )
    (comp (ref "C18")
      (value "39uF")
      (footprint "eagle-import:C0805")
      (libsource (lib "eagle-import") (part "C-USC0805"))
    )
    (comp (ref "C57")
      (value "18nF")
      (footprint "eagle-import:C0805")
      (libsource (lib "eagle-import") (part "C-USC0805"))
    )
    (comp (ref "C58")
      (value "12nF")
      (footprint "eagle-import:C0805")
      (libsource (lib "eagle-import") (part "C-USC0805"))
    )
    (comp (ref "C59")
      (value "18nF")
      (footprint "eagle-import:C0805")
      (libsource (lib "eagle-import") (part "C-USC0805"))
    )
    (comp (ref "C60")
      (value "12nF")
      (footprint "eagle-import:C0805")
      (libsource (lib "eagle-import") (part "C-USC0805"))
    )
    (comp (ref "IC9")
      (value "TLV2771CDBVR")
      (footprint "eagle-import:SOT95P280X145-5N")
      (fields (field (name "MOUSER_PART_NUMBER") "595-TLV2771CDBVR"))
      (libsource (lib "eagle-import") (part "TLV2771CDBVR"))
    )
    (comp (ref "IC10")
      (value "MCP601OT")
      (footprint "eagle-import:SOT23-5")
      (libsource (lib "eagle-import") (part "MCP601OT"))
    )
    (comp (ref "IC11")
      (value "TLV2771CDBVR")
      (footprint "eagle-import:SOT95P280X145-5N")
      (fields (field (name "MOUSER_PART_NUMBER") "595-TLV2771CDBVR"))
      (libsource (lib "eagle-import") (part "TLV2771CDBVR"))
    )
    (comp (ref "IC12")
      (value "MCP601OT")
      (footprint "eagle-import:SOT23-5")
      (libsource (lib "eagle-import") (part "MCP601OT"))
    )
    (comp (ref "R13")
      (value "10M")
      (footprint "eagle-import:R0805")
      (libsource (lib "eagle-import") (part "R-US_R0805"))
    )
    (comp (ref "R14")
      (value "13.3K")
      (footprint "eagle-import:R0805")
      (libsource (lib "eagle-import") (part "R-US_R0805"))
    )
    (comp (ref "R15")
      (value "7.5K")
      (footprint "eagle-import:R0805")
      (libsource (lib "eagle-import") (part "R-US_R0805"))
    )
    (comp (ref "R16")
      (value "10M")
      (footprint "eagle-import:R0805")
      (libsource (lib "eagle-import") (part "R-US_R0805"))
    )
    (comp (ref "R17")
      (value "13.3K")
      (footprint "eagle-import:R0805")
      (libsource (lib "eagle-import") (part "R-US_R0805"))
    )
    (comp (ref "R18")
      (value "7.5K")
      (footprint "eagle-import:R0805")
      (libsource (lib "eagle-import") (part "R-US_R0805"))
    )
    (comp (ref "R53")
      (value "1K")
      (footprint "eagle-import:R0805")
      (libsource (lib "eagle-import") (part "R-US_R0805"))
    )
    (comp (ref "R54")
      (value "1K")
      (footprint "eagle-import:R0805")
      (libsource (lib "eagle-import") (part "R-US_R0805"))
    )
    (comp (ref "C1")
      (value "150nF")
      (footprint "eagle-import:C0805")
      (libsource (lib "eagle-import") (part "C-USC0805"))
    )
    (comp (ref "C2")
      (value "0.018uF")
      (footprint "eagle-import:C0805")
      (libsource (lib "eagle-import") (part "C-USC0805"))
    )
    (comp (ref "C3")
      (value "39uF")
      (footprint "eagle-import:C0805")
      (libsource (lib "eagle-import") (part "C-USC0805"))
    )
    (comp (ref "C4")
      (value "150nF")
      (footprint "eagle-import:C0805")
      (libsource (lib "eagle-import") (part "C-USC0805"))
    )
    (comp (ref "C5")
      (value "0.018uF")
      (footprint "eagle-import:C0805")
      (libsource (lib "eagle-import") (part "C-USC0805"))
    )
    (comp (ref "C6")
      (value "39uF")
      (footprint "eagle-import:C0805")
      (libsource (lib "eagle-import") (part "C-USC0805"))
    )
    (comp (ref "C49")
      (value "18nF")
      (footprint "eagle-import:C0805")
      (libsource (lib "eagle-import") (part "C-USC0805"))
    )
    (comp (ref "C50")
      (value "12nF")
      (footprint "eagle-import:C0805")
      (libsource (lib "eagle-import") (part "C-USC0805"))
    )
    (comp (ref "C51")
      (value "18nF")
      (footprint "eagle-import:C0805")
      (libsource (lib "eagle-import") (part "C-USC0805"))
    )
    (comp (ref "C52")
      (value "12nF")
      (footprint "eagle-import:C0805")
      (libsource (lib "eagle-import") (part "C-USC0805"))
    )
    (comp (ref "IC1")
      (value "TLV2771CDBVR")
      (footprint "eagle-import:SOT95P280X145-5N")
      (fields (field (name "MOUSER_PART_NUMBER") "595-TLV2771CDBVR"))
      (libsource (lib "eagle-import") (part "TLV2771CDBVR"))
    )
    (comp (ref "IC2")
      (value "TLV2771CDBVR")
      (footprint "eagle-import:SOT95P280X145-5N")
      (fields (field (name "MOUSER_PART_NUMBER") "595-TLV2771CDBVR"))
      (libsource (lib "eagle-import") (part "TLV2771CDBVR"))
    )
    (comp (ref "IC3")
      (value "MCP601OT")
      (footprint "eagle-import:SOT23-5")
      (libsource (lib "eagle-import") (part "MCP601OT"))
    )
    (comp (ref "IC4")
      (value "MCP601OT")
      (footprint "eagle-import:SOT23-5")
      (libsource (lib "eagle-import") (part "MCP601OT"))
    )
    (comp (ref "R1")
      (value "10M")
      (footprint "eagle-import:R0805")
      (libsource (lib "eagle-import") (part "R-US_R0805"))
    )
    (comp (ref "R2")
      (value "13.3K")
      (footprint "eagle-import:R0805")
      (libsource (lib "eagle-import") (part "R-US_R0805"))
    )
    (comp (ref "R3")
      (value "7.5K")
      (footprint "eagle-import:R0805")
      (libsource (lib "eagle-import") (part "R-US_R0805"))
    )
    (comp (ref "R4")
      (value "10M")
      (footprint "eagle-import:R0805")
      (libsource (lib "eagle-import") (part "R-US_R0805"))
    )
    (comp (ref "R5")
      (value "13.3K")
      (footprint "eagle-import:R0805")
      (libsource (lib "eagle-import") (part "R-US_R0805"))
    )
    (comp (ref "R6")
      (value "7.5K")
      (footprint "eagle-import:R0805")
      (libsource (lib "eagle-import") (part "R-US_R0805"))
    )
    (comp (ref "R49")
      (value "1K")
      (footprint "eagle-import:R0805")
      (libsource (lib "eagle-import") (part "R-US_R0805"))
    )
    (comp (ref "R50")
      (value "1K")
      (footprint "eagle-import:R0805")
      (libsource (lib "eagle-import") (part "R-US_R0805"))
    )
    (comp (ref "C37")
      (value "150nF")
      (footprint "eagle-import:C0805")
      (libsource (lib "eagle-import") (part "C-USC0805"))
    )
    (comp (ref "C38")
      (value "0.018uF")
      (footprint "eagle-import:C0805")
      (libsource (lib "eagle-import") (part "C-USC0805"))
    )
    (comp (ref "C39")
      (value "39uF")
      (footprint "eagle-import:C0805")
      (libsource (lib "eagle-import") (part "C-USC0805"))
    )
    (comp (ref "C40")
      (value "150nF")
      (footprint "eagle-import:C0805")
      (libsource (lib "eagle-import") (part "C-USC0805"))
    )
    (comp (ref "C41")
      (value "0.018uF")
      (footprint "eagle-import:C0805")
      (libsource (lib "eagle-import") (part "C-USC0805"))
    )
    (comp (ref "C42")
      (value "39uF")
      (footprint "eagle-import:C0805")
      (libsource (lib "eagle-import") (part "C-USC0805"))
    )
    (comp (ref "C73")
      (value "18nF")
      (footprint "eagle-import:C0805")
      (libsource (lib "eagle-import") (part "C-USC0805"))
    )
    (comp (ref "C74")
      (value "12nF")
      (footprint "eagle-import:C0805")
      (libsource (lib "eagle-import") (part "C-USC0805"))
    )
    (comp (ref "C75")
      (value "18nF")
      (footprint "eagle-import:C0805")
      (libsource (lib "eagle-import") (part "C-USC0805"))
    )
    (comp (ref "C76")
      (value "12nF")
      (footprint "eagle-import:C0805")
      (libsource (lib "eagle-import") (part "C-USC0805"))
    )
    (comp (ref "IC25")
      (value "TLV2771CDBVR")
      (footprint "eagle-import:SOT95P280X145-5N")
      (fields (field (name "MOUSER_PART_NUMBER") "595-TLV2771CDBVR"))
      (libsource (lib "eagle-import") (part "TLV2771CDBVR"))
    )
    (comp (ref "IC26")
      (value "MCP601OT")
      (footprint "eagle-import:SOT23-5")
      (libsource (lib "eagle-import") (part "MCP601OT"))
    )
    (comp (ref "IC27")
      (value "TLV2771CDBVR")
      (footprint "eagle-import:SOT95P280X145-5N")
      (fields (field (name "MOUSER_PART_NUMBER") "595-TLV2771CDBVR"))
      (libsource (lib "eagle-import") (part "TLV2771CDBVR"))
    )
    (comp (ref "IC28")
      (value "MCP601OT")
      (footprint "eagle-import:SOT23-5")
      (libsource (lib "eagle-import") (part "MCP601OT"))
    )
    (comp (ref "R37")
      (value "10M")
      (footprint "eagle-import:R0805")
      (libsource (lib "eagle-import") (part "R-US_R0805"))
    )
    (comp (ref "R38")
      (value "13.3K")
      (footprint "eagle-import:R0805")
      (libsource (lib "eagle-import") (part "R-US_R0805"))
    )
    (comp (ref "R39")
      (value "7.5K")
      (footprint "eagle-import:R0805")
      (libsource (lib "eagle-import") (part "R-US_R0805"))
    )
    (comp (ref "R40")
      (value "10M")
      (footprint "eagle-import:R0805")
      (libsource (lib "eagle-import") (part "R-US_R0805"))
    )
    (comp (ref "R41")
      (value "13.3K")
      (footprint "eagle-import:R0805")
      (libsource (lib "eagle-import") (part "R-US_R0805"))
    )
    (comp (ref "R42")
      (value "7.5K")
      (footprint "eagle-import:R0805")
      (libsource (lib "eagle-import") (part "R-US_R0805"))
    )
    (comp (ref "R61")
      (value "1K")
      (footprint "eagle-import:R0805")
      (libsource (lib "eagle-import") (part "R-US_R0805"))
    )
    (comp (ref "R62")
      (value "1K")
      (footprint "eagle-import:R0805")
      (libsource (lib "eagle-import") (part "R-US_R0805"))
    )
    (comp (ref "C19")
      (value "150nF")
      (footprint "eagle-import:C0805")
      (libsource (lib "eagle-import") (part "C-USC0805"))
    )
    (comp (ref "C20")
      (value "0.018uF")
      (footprint "eagle-import:C0805")
      (libsource (lib "eagle-import") (part "C-USC0805"))
    )
    (comp (ref "C21")
      (value "39uF")
      (footprint "eagle-import:C0805")
      (libsource (lib "eagle-import") (part "C-USC0805"))
    )
    (comp (ref "C22")
      (value "150nF")
      (footprint "eagle-import:C0805")
      (libsource (lib "eagle-import") (part "C-USC0805"))
    )
    (comp (ref "C23")
      (value "0.018uF")
      (footprint "eagle-import:C0805")
      (libsource (lib "eagle-import") (part "C-USC0805"))
    )
    (comp (ref "C24")
      (value "39uF")
      (footprint "eagle-import:C0805")
      (libsource (lib "eagle-import") (part "C-USC0805"))
    )
    (comp (ref "C61")
      (value "18nF")
      (footprint "eagle-import:C0805")
      (libsource (lib "eagle-import") (part "C-USC0805"))
    )
    (comp (ref "C62")
      (value "12nF")
      (footprint "eagle-import:C0805")
      (libsource (lib "eagle-import") (part "C-USC0805"))
    )
    (comp (ref "C63")
      (value "18nF")
      (footprint "eagle-import:C0805")
      (libsource (lib "eagle-import") (part "C-USC0805"))
    )
    (comp (ref "C64")
      (value "12nF")
      (footprint "eagle-import:C0805")
      (libsource (lib "eagle-import") (part "C-USC0805"))
    )
    (comp (ref "IC13")
      (value "TLV2771CDBVR")
      (footprint "eagle-import:SOT95P280X145-5N")
      (fields (field (name "MOUSER_PART_NUMBER") "595-TLV2771CDBVR"))
      (libsource (lib "eagle-import") (part "TLV2771CDBVR"))
    )
    (comp (ref "IC14")
      (value "MCP601OT")
      (footprint "eagle-import:SOT23-5")
      (libsource (lib "eagle-import") (part "MCP601OT"))
    )
    (comp (ref "IC15")
      (value "TLV2771CDBVR")
      (footprint "eagle-import:SOT95P280X145-5N")
      (fields (field (name "MOUSER_PART_NUMBER") "595-TLV2771CDBVR"))
      (libsource (lib "eagle-import") (part "TLV2771CDBVR"))
    )
    (comp (ref "IC16")
      (value "MCP601OT")
      (footprint "eagle-import:SOT23-5")
      (libsource (lib "eagle-import") (part "MCP601OT"))
    )
    (comp (ref "R19")
      (value "10M")
      (footprint "eagle-import:R0805")
      (libsource (lib "eagle-import") (part "R-US_R0805"))
    )
    (comp (ref "R20")
      (value "13.3K")
      (footprint "eagle-import:R0805")
      (libsource (lib "eagle-import") (part "R-US_R0805"))
    )
    (comp (ref "R21")
      (value "7.5K")
      (footprint "eagle-import:R0805")
      (libsource (lib "eagle-import") (part "R-US_R0805"))
    )
    (comp (ref "R22")
      (value "10M")
      (footprint "eagle-import:R0805")
      (libsource (lib "eagle-import") (part "R-US_R0805"))
    )
    (comp (ref "R23")
      (value "13.3K")
      (footprint "eagle-import:R0805")
      (libsource (lib "eagle-import") (part "R-US_R0805"))
    )
    (comp (ref "R24")
      (value "7.5K")
      (footprint "eagle-import:R0805")
      (libsource (lib "eagle-import") (part "R-US_R0805"))
    )
    (comp (ref "R55")
      (value "1K")
      (footprint "eagle-import:R0805")
      (libsource (lib "eagle-import") (part "R-US_R0805"))
    )
    (comp (ref "R56")
      (value "1K")
      (footprint "eagle-import:R0805")
      (libsource (lib "eagle-import") (part "R-US_R0805"))
    )
    (comp (ref "C43")
      (value "150nF")
      (footprint "eagle-import:C0805")
      (libsource (lib "eagle-import") (part "C-USC0805"))
    )
    (comp (ref "C44")
      (value "0.018uF")
      (footprint "eagle-import:C0805")
      (libsource (lib "eagle-import") (part "C-USC0805"))
    )
    (comp (ref "C45")
      (value "39uF")
      (footprint "eagle-import:C0805")
      (libsource (lib "eagle-import") (part "C-USC0805"))
    )
    (comp (ref "C46")
      (value "150nF")
      (footprint "eagle-import:C0805")
      (libsource (lib "eagle-import") (part "C-USC0805"))
    )
    (comp (ref "C47")
      (value "0.018uF")
      (footprint "eagle-import:C0805")
      (libsource (lib "eagle-import") (part "C-USC0805"))
    )
    (comp (ref "C48")
      (value "39uF")
      (footprint "eagle-import:C0805")
      (libsource (lib "eagle-import") (part "C-USC0805"))
    )
    (comp (ref "C77")
      (value "18nF")
      (footprint "eagle-import:C0805")
      (libsource (lib "eagle-import") (part "C-USC0805"))
    )
    (comp (ref "C78")
      (value "12nF")
      (footprint "eagle-import:C0805")
      (libsource (lib "eagle-import") (part "C-USC0805"))
    )
    (comp (ref "C79")
      (value "18nF")
      (footprint "eagle-import:C0805")
      (libsource (lib "eagle-import") (part "C-USC0805"))
    )
    (comp (ref "C80")
      (value "12nF")
      (footprint "eagle-import:C0805")
      (libsource (lib "eagle-import") (part "C-USC0805"))
    )
    (comp (ref "IC29")
      (value "TLV2771CDBVR")
      (footprint "eagle-import:SOT95P280X145-5N")
      (fields (field (name "MOUSER_PART_NUMBER") "595-TLV2771CDBVR"))
      (libsource (lib "eagle-import") (part "TLV2771CDBVR"))
    )
    (comp (ref "IC30")
      (value "MCP601OT")
      (footprint "eagle-import:SOT23-5")
      (libsource (lib "eagle-import") (part "MCP601OT"))
    )
    (comp (ref "IC31")
      (value "TLV2771CDBVR")
      (footprint "eagle-import:SOT95P280X145-5N")
      (fields (field (name "MOUSER_PART_NUMBER") "595-TLV2771CDBVR"))
      (libsource (lib "eagle-import") (part "TLV2771CDBVR"))
    )
    (comp (ref "IC32")
      (value "MCP601OT")
      (footprint "eagle-import:SOT23-5")
      (libsource (lib "eagle-import") (part "MCP601OT"))
    )
    (comp (ref "R43")
      (value "10M")
      (footprint "eagle-import:R0805")
      (libsource (lib "eagle-import") (part "R-US_R0805"))
    )
    (comp (ref "R44")
      (value "13.3K")
      (footprint "eagle-import:R0805")
      (libsource (lib "eagle-import") (part "R-US_R0805"))
    )
    (comp (ref "R45")
      (value "7.5K")
      (footprint "eagle-import:R0805")
      (libsource (lib "eagle-import") (part "R-US_R0805"))
    )
    (comp (ref "R46")
      (value "10M")
      (footprint "eagle-import:R0805")
      (libsource (lib "eagle-import") (part "R-US_R0805"))
    )
    (comp (ref "R47")
      (value "13.3K")
      (footprint "eagle-import:R0805")
      (libsource (lib "eagle-import") (part "R-US_R0805"))
    )
    (comp (ref "R48")
      (value "7.5K")
      (footprint "eagle-import:R0805")
      (libsource (lib "eagle-import") (part "R-US_R0805"))
    )
    (comp (ref "R63")
      (value "1K")
      (footprint "eagle-import:R0805")
      (libsource (lib "eagle-import") (part "R-US_R0805"))
    )
    (comp (ref "R64")
      (value "1K")
      (footprint "eagle-import:R0805")
      (libsource (lib "eagle-import") (part "R-US_R0805"))
    )
    (comp (ref "C31")
      (value "150nF")
      (footprint "eagle-import:C0805")
      (libsource (lib "eagle-import") (part "C-USC0805"))
    )
    (comp (ref "C32")
      (value "0.018uF")
      (footprint "eagle-import:C0805")
      (libsource (lib "eagle-import") (part "C-USC0805"))
    )
    (comp (ref "C33")
      (value "39uF")
      (footprint "eagle-import:C0805")
      (libsource (lib "eagle-import") (part "C-USC0805"))
    )
    (comp (ref "C34")
      (value "150nF")
      (footprint "eagle-import:C0805")
      (libsource (lib "eagle-import") (part "C-USC0805"))
    )
    (comp (ref "C35")
      (value "0.018uF")
      (footprint "eagle-import:C0805")
      (libsource (lib "eagle-import") (part "C-USC0805"))
    )
    (comp (ref "C36")
      (value "39uF")
      (footprint "eagle-import:C0805")
      (libsource (lib "eagle-import") (part "C-USC0805"))
    )
    (comp (ref "C69")
      (value "18nF")
      (footprint "eagle-import:C0805")
      (libsource (lib "eagle-import") (part "C-USC0805"))
    )
    (comp (ref "C70")
      (value "12nF")
      (footprint "eagle-import:C0805")
      (libsource (lib "eagle-import") (part "C-USC0805"))
    )
    (comp (ref "C71")
      (value "18nF")
      (footprint "eagle-import:C0805")
      (libsource (lib "eagle-import") (part "C-USC0805"))
    )
    (comp (ref "C72")
      (value "12nF")
      (footprint "eagle-import:C0805")
      (libsource (lib "eagle-import") (part "C-USC0805"))
    )
    (comp (ref "IC21")
      (value "TLV2771CDBVR")
      (footprint "eagle-import:SOT95P280X145-5N")
      (fields (field (name "MOUSER_PART_NUMBER") "595-TLV2771CDBVR"))
      (libsource (lib "eagle-import") (part "TLV2771CDBVR"))
    )
    (comp (ref "IC22")
      (value "MCP601OT")
      (footprint "eagle-import:SOT23-5")
      (libsource (lib "eagle-import") (part "MCP601OT"))
    )
    (comp (ref "IC23")
      (value "TLV2771CDBVR")
      (footprint "eagle-import:SOT95P280X145-5N")
      (fields (field (name "MOUSER_PART_NUMBER") "595-TLV2771CDBVR"))
      (libsource (lib "eagle-import") (part "TLV2771CDBVR"))
    )
    (comp (ref "IC24")
      (value "MCP601OT")
      (footprint "eagle-import:SOT23-5")
      (libsource (lib "eagle-import") (part "MCP601OT"))
    )
    (comp (ref "R31")
      (value "10M")
      (footprint "eagle-import:R0805")
      (libsource (lib "eagle-import") (part "R-US_R0805"))
    )
    (comp (ref "R32")
      (value "13.3K")
      (footprint "eagle-import:R0805")
      (libsource (lib "eagle-import") (part "R-US_R0805"))
    )
    (comp (ref "R33")
      (value "7.5K")
      (footprint "eagle-import:R0805")
      (libsource (lib "eagle-import") (part "R-US_R0805"))
    )
    (comp (ref "R34")
      (value "10M")
      (footprint "eagle-import:R0805")
      (libsource (lib "eagle-import") (part "R-US_R0805"))
    )
    (comp (ref "R35")
      (value "13.3K")
      (footprint "eagle-import:R0805")
      (libsource (lib "eagle-import") (part "R-US_R0805"))
    )
    (comp (ref "R36")
      (value "7.5K")
      (footprint "eagle-import:R0805")
      (libsource (lib "eagle-import") (part "R-US_R0805"))
    )
    (comp (ref "R59")
      (value "1K")
      (footprint "eagle-import:R0805")
      (libsource (lib "eagle-import") (part "R-US_R0805"))
    )
    (comp (ref "R60")
      (value "1K")
      (footprint "eagle-import:R0805")
      (libsource (lib "eagle-import") (part "R-US_R0805"))
    )
    (comp (ref "C7")
      (value "150nF")
      (footprint "eagle-import:C0805")
      (libsource (lib "eagle-import") (part "C-USC0805"))
    )
    (comp (ref "C8")
      (value "0.018uF")
      (footprint "eagle-import:C0805")
      (libsource (lib "eagle-import") (part "C-USC0805"))
    )
    (comp (ref "C9")
      (value "39uF")
      (footprint "eagle-import:C0805")
      (libsource (lib "eagle-import") (part "C-USC0805"))
    )
    (comp (ref "C10")
      (value "150nF")
      (footprint "eagle-import:C0805")
      (libsource (lib "eagle-import") (part "C-USC0805"))
    )
    (comp (ref "C11")
      (value "0.018uF")
      (footprint "eagle-import:C0805")
      (libsource (lib "eagle-import") (part "C-USC0805"))
    )
    (comp (ref "C12")
      (value "39uF")
      (footprint "eagle-import:C0805")
      (libsource (lib "eagle-import") (part "C-USC0805"))
    )
    (comp (ref "C53")
      (value "18nF")
      (footprint "eagle-import:C0805")
      (libsource (lib "eagle-import") (part "C-USC0805"))
    )
    (comp (ref "C54")
      (value "12nF")
      (footprint "eagle-import:C0805")
      (libsource (lib "eagle-import") (part "C-USC0805"))
    )
    (comp (ref "C55")
      (value "18nF")
      (footprint "eagle-import:C0805")
      (libsource (lib "eagle-import") (part "C-USC0805"))
    )
    (comp (ref "C56")
      (value "12nF")
      (footprint "eagle-import:C0805")
      (libsource (lib "eagle-import") (part "C-USC0805"))
    )
    (comp (ref "IC5")
      (value "TLV2771CDBVR")
      (footprint "eagle-import:SOT95P280X145-5N")
      (fields (field (name "MOUSER_PART_NUMBER") "595-TLV2771CDBVR"))
      (libsource (lib "eagle-import") (part "TLV2771CDBVR"))
    )
    (comp (ref "IC6")
      (value "MCP601OT")
      (footprint "eagle-import:SOT23-5")
      (libsource (lib "eagle-import") (part "MCP601OT"))
    )
    (comp (ref "IC7")
      (value "TLV2771CDBVR")
      (footprint "eagle-import:SOT95P280X145-5N")
      (fields (field (name "MOUSER_PART_NUMBER") "595-TLV2771CDBVR"))
      (libsource (lib "eagle-import") (part "TLV2771CDBVR"))
    )
    (comp (ref "IC8")
      (value "MCP601OT")
      (footprint "eagle-import:SOT23-5")
      (libsource (lib "eagle-import") (part "MCP601OT"))
    )
    (comp (ref "R7")
      (value "10M")
      (footprint "eagle-import:R0805")
      (libsource (lib "eagle-import") (part "R-US_R0805"))
    )
    (comp (ref "R8")
      (value "13.3K")
      (footprint "eagle-import:R0805")
      (libsource (lib "eagle-import") (part "R-US_R0805"))
    )
    (comp (ref "R9")
      (value "7.5K")
      (footprint "eagle-import:R0805")
      (libsource (lib "eagle-import") (part "R-US_R0805"))
    )
    (comp (ref "R10")
      (value "10M")
      (footprint "eagle-import:R0805")
      (libsource (lib "eagle-import") (part "R-US_R0805"))
    )
    (comp (ref "R11")
      (value "13.3K")
      (footprint "eagle-import:R0805")
      (libsource (lib "eagle-import") (part "R-US_R0805"))
    )
    (comp (ref "R12")
      (value "7.5K")
      (footprint "eagle-import:R0805")
      (libsource (lib "eagle-import") (part "R-US_R0805"))
    )
    (comp (ref "R51")
      (value "1K")
      (footprint "eagle-import:R0805")
      (libsource (lib "eagle-import") (part "R-US_R0805"))
    )
    (comp (ref "R52")
      (value "1K")
      (footprint "eagle-import:R0805")
      (libsource (lib "eagle-import") (part "R-US_R0805"))
    )
    (comp (ref "C81")
      (value "1uF")
      (footprint "eagle-import:C0805")
      (libsource (lib "eagle-import") (part "C-USC0805"))
    )
    (comp (ref "C82")
      (value "1uF")
      (footprint "eagle-import:C0805")
      (libsource (lib "eagle-import") (part "C-USC0805"))
    )
    (comp (ref "C83")
      (value "1uF")
      (footprint "eagle-import:C0805")
      (libsource (lib "eagle-import") (part "C-USC0805"))
    )
    (comp (ref "C84")
      (value "1uF")
      (footprint "eagle-import:C0805")
      (libsource (lib "eagle-import") (part "C-USC0805"))
    )
    (comp (ref "C85")
      (value "1uF")
      (footprint "eagle-import:C0805")
      (libsource (lib "eagle-import") (part "C-USC0805"))
    )
    (comp (ref "C86")
      (value "1uF")
      (footprint "eagle-import:C0805")
      (libsource (lib "eagle-import") (part "C-USC0805"))
    )
    (comp (ref "C87")
      (value "1uF")
      (footprint "eagle-import:C0805")
      (libsource (lib "eagle-import") (part "C-USC0805"))
    )
    (comp (ref "C88")
      (value "1uF")
      (footprint "eagle-import:C0805")
      (libsource (lib "eagle-import") (part "C-USC0805"))
    )
    (comp (ref "C89")
      (value "1uF")
      (footprint "eagle-import:C0805")
      (libsource (lib "eagle-import") (part "C-USC0805"))
    )
    (comp (ref "C90")
      (value "1uF")
      (footprint "eagle-import:C0805")
      (libsource (lib "eagle-import") (part "C-USC0805"))
    )
    (comp (ref "C91")
      (value "1uF")
      (footprint "eagle-import:C0805")
      (libsource (lib "eagle-import") (part "C-USC0805"))
    )
    (comp (ref "C92")
      (value "1uF")
      (footprint "eagle-import:C0805")
      (libsource (lib "eagle-import") (part "C-USC0805"))
    )
    (comp (ref "C93")
      (value "1uF")
      (footprint "eagle-import:C0805")
      (libsource (lib "eagle-import") (part "C-USC0805"))
    )
    (comp (ref "C94")
      (value "1uF")
      (footprint "eagle-import:C0805")
      (libsource (lib "eagle-import") (part "C-USC0805"))
    )
    (comp (ref "C95")
      (value "1uF")
      (footprint "eagle-import:C0805")
      (libsource (lib "eagle-import") (part "C-USC0805"))
    )
    (comp (ref "C96")
      (value "1uF")
      (footprint "eagle-import:C0805")
      (libsource (lib "eagle-import") (part "C-USC0805"))
    )
    (comp (ref "U1")
      (value "REF5025AID")
      (footprint "eagle-import:D8")
      (fields
        (field (name "GENERIC_PART_NUMBER") "REF5025")
        (field (name "MANUFACTURER") "Texas Instruments")
      )
      (libsource (lib "eagle-import") (part "REF5025AID"))
    )
    (comp (ref "U2")
      (value "REF5025AID")
      (footprint "eagle-import:D8")
      (fields
        (field (name "GENERIC_PART_NUMBER") "REF5025")
        (field (name "MANUFACTURER") "Texas Instruments")
      )
      (libsource (lib "eagle-import") (part "REF5025AID"))
    )
    (comp (ref "U3")
      (value "REF5025AID")
      (footprint "eagle-import:D8")
      (fields
        (field (name "GENERIC_PART_NUMBER") "REF5025")
        (field (name "MANUFACTURER") "Texas Instruments")
      )
      (libsource (lib "eagle-import") (part "REF5025AID"))
    )
    (comp (ref "U4")
      (value "REF5025AID")
      (footprint "eagle-import:D8")
      (fields
        (field (name "GENERIC_PART_NUMBER") "REF5025")
        (field (name "MANUFACTURER") "Texas Instruments")
      )
      (libsource (lib "eagle-import") (part "REF5025AID"))
    )
    (comp (ref "U5")
      (value "REF5025AID")
      (footprint "eagle-import:D8")
      (fields
        (field (name "GENERIC_PART_NUMBER") "REF5025")
        (field (name "MANUFACTURER") "Texas Instruments")
      )
      (libsource (lib "eagle-import") (part "REF5025AID"))
    )
    (comp (ref "U6")
      (value "REF5025AID")
      (footprint "eagle-import:D8")
      (fields
        (field (name "GENERIC_PART_NUMBER") "REF5025")
        (field (name "MANUFACTURER") "Texas Instruments")
      )
      (libsource (lib "eagle-import") (part "REF5025AID"))
    )
    (comp (ref "U7")
      (value "REF5025AID")
      (footprint "eagle-import:D8")
      (fields
        (field (name "GENERIC_PART_NUMBER") "REF5025")
        (field (name "MANUFACTURER") "Texas Instruments")
      )
      (libsource (lib "eagle-import") (part "REF5025AID"))
    )
    (comp (ref "U8")
      (value "REF5025AID")
      (footprint "eagle-import:D8")
      (fields
        (field (name "GENERIC_PART_NUMBER") "REF5025")
        (field (name "MANUFACTURER") "Texas Instruments")
      )
      (libsource (lib "eagle-import") (part "REF5025AID"))
    )
    (comp (ref "C97")
      (value "1uF")
      (footprint "eagle-import:C0805")
      (libsource (lib "eagle-import") (part "C-USC0805"))
    )
    (comp (ref "C98")
      (value "1uF")
      (footprint "eagle-import:C0805")
      (libsource (lib "eagle-import") (part "C-USC0805"))
    )
    (comp (ref "C99")
      (value "1uF")
      (footprint "eagle-import:C0805")
      (libsource (lib "eagle-import") (part "C-USC0805"))
    )
    (comp (ref "C100")
      (value "1uF")
      (footprint "eagle-import:C0805")
      (libsource (lib "eagle-import") (part "C-USC0805"))
    )
    (comp (ref "C101")
      (value "1uF")
      (footprint "eagle-import:C0805")
      (libsource (lib "eagle-import") (part "C-USC0805"))
    )
    (comp (ref "C102")
      (value "1uF")
      (footprint "eagle-import:C0805")
      (libsource (lib "eagle-import") (part "C-USC0805"))
    )
    (comp (ref "C103")
      (value "1uF")
      (footprint "eagle-import:C0805")
      (libsource (lib "eagle-import") (part "C-USC0805"))
    )
    (comp (ref "C104")
      (value "1uF")
      (footprint "eagle-import:C0805")
      (libsource (lib "eagle-import") (part "C-USC0805"))
    )
    (comp (ref "C105")
      (value "1uF")
      (footprint "eagle-import:C0805")
      (libsource (lib "eagle-import") (part "C-USC0805"))
    )
    (comp (ref "C106")
      (value "1uF")
      (footprint "eagle-import:C0805")
      (libsource (lib "eagle-import") (part "C-USC0805"))
    )
    (comp (ref "C107")
      (value "1uF")
      (footprint "eagle-import:C0805")
      (libsource (lib "eagle-import") (part "C-USC0805"))
    )
    (comp (ref "C108")
      (value "1uF")
      (footprint "eagle-import:C0805")
      (libsource (lib "eagle-import") (part "C-USC0805"))
    )
    (comp (ref "C109")
      (value "1uF")
      (footprint "eagle-import:C0805")
      (libsource (lib "eagle-import") (part "C-USC0805"))
    )
    (comp (ref "C110")
      (value "1uF")
      (footprint "eagle-import:C0805")
      (libsource (lib "eagle-import") (part "C-USC0805"))
    )
    (comp (ref "C111")
      (value "1uF")
      (footprint "eagle-import:C0805")
      (libsource (lib "eagle-import") (part "C-USC0805"))
    )
    (comp (ref "C112")
      (value "1uF")
      (footprint "eagle-import:C0805")
      (libsource (lib "eagle-import") (part "C-USC0805"))
    )
    (comp (ref "U9")
      (value "REF5025AID")
      (footprint "eagle-import:D8")
      (fields
        (field (name "GENERIC_PART_NUMBER") "REF5025")
        (field (name "MANUFACTURER") "Texas Instruments")
      )
      (libsource (lib "eagle-import") (part "REF5025AID"))
    )
    (comp (ref "U10")
      (value "REF5025AID")
      (footprint "eagle-import:D8")
      (fields
        (field (name "GENERIC_PART_NUMBER") "REF5025")
        (field (name "MANUFACTURER") "Texas Instruments")
      )
      (libsource (lib "eagle-import") (part "REF5025AID"))
    )
    (comp (ref "U11")
      (value "REF5025AID")
      (footprint "eagle-import:D8")
      (fields
        (field (name "GENERIC_PART_NUMBER") "REF5025")
        (field (name "MANUFACTURER") "Texas Instruments")
      )
      (libsource (lib "eagle-import") (part "REF5025AID"))
    )
    (comp (ref "U12")
      (value "REF5025AID")
      (footprint "eagle-import:D8")
      (fields
        (field (name "GENERIC_PART_NUMBER") "REF5025")
        (field (name "MANUFACTURER") "Texas Instruments")
      )
      (libsource (lib "eagle-import") (part "REF5025AID"))
    )
    (comp (ref "U13")
      (value "REF5025AID")
      (footprint "eagle-import:D8")
      (fields
        (field (name "GENERIC_PART_NUMBER") "REF5025")
        (field (name "MANUFACTURER") "Texas Instruments")
      )
      (libsource (lib "eagle-import") (part "REF5025AID"))
    )
    (comp (ref "U14")
      (value "REF5025AID")
      (footprint "eagle-import:D8")
      (fields
        (field (name "GENERIC_PART_NUMBER") "REF5025")
        (field (name "MANUFACTURER") "Texas Instruments")
      )
      (libsource (lib "eagle-import") (part "REF5025AID"))
    )
    (comp (ref "U15")
      (value "REF5025AID")
      (footprint "eagle-import:D8")
      (fields
        (field (name "GENERIC_PART_NUMBER") "REF5025")
        (field (name "MANUFACTURER") "Texas Instruments")
      )
      (libsource (lib "eagle-import") (part "REF5025AID"))
    )
    (comp (ref "U16")
      (value "REF5025AID")
      (footprint "eagle-import:D8")
      (fields
        (field (name "GENERIC_PART_NUMBER") "REF5025")
        (field (name "MANUFACTURER") "Texas Instruments")
      )
      (libsource (lib "eagle-import") (part "REF5025AID"))
    )
    (comp (ref "C25")
      (value "150nF")
      (footprint "eagle-import:C0805")
      (libsource (lib "eagle-import") (part "C-USC0805"))
    )
    (comp (ref "C26")
      (value "0.018uF")
      (footprint "eagle-import:C0805")
      (libsource (lib "eagle-import") (part "C-USC0805"))
    )
    (comp (ref "C27")
      (value "39uF")
      (footprint "eagle-import:C0805")
      (libsource (lib "eagle-import") (part "C-USC0805"))
    )
    (comp (ref "C28")
      (value "150nF")
      (footprint "eagle-import:C0805")
      (libsource (lib "eagle-import") (part "C-USC0805"))
    )
    (comp (ref "C29")
      (value "0.018uF")
      (footprint "eagle-import:C0805")
      (libsource (lib "eagle-import") (part "C-USC0805"))
    )
    (comp (ref "C30")
      (value "39uF")
      (footprint "eagle-import:C0805")
      (libsource (lib "eagle-import") (part "C-USC0805"))
    )
    (comp (ref "C65")
      (value "18nF")
      (footprint "eagle-import:C0805")
      (libsource (lib "eagle-import") (part "C-USC0805"))
    )
    (comp (ref "C66")
      (value "12nF")
      (footprint "eagle-import:C0805")
      (libsource (lib "eagle-import") (part "C-USC0805"))
    )
    (comp (ref "C67")
      (value "18nF")
      (footprint "eagle-import:C0805")
      (libsource (lib "eagle-import") (part "C-USC0805"))
    )
    (comp (ref "C68")
      (value "12nF")
      (footprint "eagle-import:C0805")
      (libsource (lib "eagle-import") (part "C-USC0805"))
    )
    (comp (ref "IC17")
      (value "TLV2771CDBVR")
      (footprint "eagle-import:SOT95P280X145-5N")
      (fields (field (name "MOUSER_PART_NUMBER") "595-TLV2771CDBVR"))
      (libsource (lib "eagle-import") (part "TLV2771CDBVR"))
    )
    (comp (ref "IC18")
      (value "MCP601OT")
      (footprint "eagle-import:SOT23-5")
      (libsource (lib "eagle-import") (part "MCP601OT"))
    )
    (comp (ref "IC19")
      (value "TLV2771CDBVR")
      (footprint "eagle-import:SOT95P280X145-5N")
      (fields (field (name "MOUSER_PART_NUMBER") "595-TLV2771CDBVR"))
      (libsource (lib "eagle-import") (part "TLV2771CDBVR"))
    )
    (comp (ref "IC20")
      (value "MCP601OT")
      (footprint "eagle-import:SOT23-5")
      (libsource (lib "eagle-import") (part "MCP601OT"))
    )
    (comp (ref "R25")
      (value "10M")
      (footprint "eagle-import:R0805")
      (libsource (lib "eagle-import") (part "R-US_R0805"))
    )
    (comp (ref "R26")
      (value "13.3K")
      (footprint "eagle-import:R0805")
      (libsource (lib "eagle-import") (part "R-US_R0805"))
    )
    (comp (ref "R27")
      (value "7.5K")
      (footprint "eagle-import:R0805")
      (libsource (lib "eagle-import") (part "R-US_R0805"))
    )
    (comp (ref "R28")
      (value "10M")
      (footprint "eagle-import:R0805")
      (libsource (lib "eagle-import") (part "R-US_R0805"))
    )
    (comp (ref "R29")
      (value "13.3K")
      (footprint "eagle-import:R0805")
      (libsource (lib "eagle-import") (part "R-US_R0805"))
    )
    (comp (ref "R30")
      (value "7.5K")
      (footprint "eagle-import:R0805")
      (libsource (lib "eagle-import") (part "R-US_R0805"))
    )
    (comp (ref "R57")
      (value "1K")
      (footprint "eagle-import:R0805")
      (libsource (lib "eagle-import") (part "R-US_R0805"))
    )
    (comp (ref "R58")
      (value "1K")
      (footprint "eagle-import:R0805")
      (libsource (lib "eagle-import") (part "R-US_R0805"))
    )
    (comp (ref "J1")
      (value "1985027")
      (footprint "eagle-import:1985027")
      (fields (field (name "MOUSER_PART_NUMBER") "651-1985027"))
      (libsource (lib "eagle-import") (part "1985027"))
    )
    (comp (ref "J2")
      (value "1985027")
      (footprint "eagle-import:1985027")
      (fields (field (name "MOUSER_PART_NUMBER") "651-1985027"))
      (libsource (lib "eagle-import") (part "1985027"))
    )
    (comp (ref "J3")
      (value "1985027")
      (footprint "eagle-import:1985027")
      (fields (field (name "MOUSER_PART_NUMBER") "651-1985027"))
      (libsource (lib "eagle-import") (part "1985027"))
    )
    (comp (ref "J4")
      (value "1985027")
      (footprint "eagle-import:1985027")
      (fields (field (name "MOUSER_PART_NUMBER") "651-1985027"))
      (libsource (lib "eagle-import") (part "1985027"))
    )
    (comp (ref "JP1")
      (value "PINHD-2X20")
      (footprint "eagle-import:2X20")
      (libsource (lib "eagle-import") (part "PINHD-2X20"))
    )
  )
  (nets
    (net (code "1") (name "+5V") (class "Default")
      (node (ref "C101") (pin "1") (pinfunction "1_1") (pintype "passive"))
      (node (ref "C103") (pin "1") (pinfunction "1_1") (pintype "passive"))
      (node (ref "C105") (pin "1") (pinfunction "1_1") (pintype "passive"))
      (node (ref "C107") (pin "1") (pinfunction "1_1") (pintype "passive"))
      (node (ref "C109") (pin "1") (pinfunction "1_1") (pintype "passive"))
      (node (ref "C111") (pin "1") (pinfunction "1_1") (pintype "passive"))
      (node (ref "C81") (pin "1") (pinfunction "1_1") (pintype "passive"))
      (node (ref "C83") (pin "1") (pinfunction "1_1") (pintype "passive"))
      (node (ref "C85") (pin "1") (pinfunction "1_1") (pintype "passive"))
      (node (ref "C87") (pin "1") (pinfunction "1_1") (pintype "passive"))
      (node (ref "C89") (pin "1") (pinfunction "1_1") (pintype "passive"))
      (node (ref "C91") (pin "1") (pinfunction "1_1") (pintype "passive"))
      (node (ref "C93") (pin "1") (pinfunction "1_1") (pintype "passive"))
      (node (ref "C95") (pin "1") (pinfunction "1_1") (pintype "passive"))
      (node (ref "C97") (pin "1") (pinfunction "1_1") (pintype "passive"))
      (node (ref "C99") (pin "1") (pinfunction "1_1") (pintype "passive"))
      (node (ref "IC1") (pin "5") (pinfunction "VDD_5") (pintype "bidirectional"))
      (node (ref "IC10") (pin "5") (pinfunction "V+_5") (pintype "power_in"))
      (node (ref "IC11") (pin "5") (pinfunction "VDD_5") (pintype "bidirectional"))
      (node (ref "IC12") (pin "5") (pinfunction "V+_5") (pintype "power_in"))
      (node (ref "IC13") (pin "5") (pinfunction "VDD_5") (pintype "bidirectional"))
      (node (ref "IC14") (pin "5") (pinfunction "V+_5") (pintype "power_in"))
      (node (ref "IC15") (pin "5") (pinfunction "VDD_5") (pintype "bidirectional"))
      (node (ref "IC16") (pin "5") (pinfunction "V+_5") (pintype "power_in"))
      (node (ref "IC17") (pin "5") (pinfunction "VDD_5") (pintype "bidirectional"))
      (node (ref "IC18") (pin "5") (pinfunction "V+_5") (pintype "power_in"))
      (node (ref "IC19") (pin "5") (pinfunction "VDD_5") (pintype "bidirectional"))
      (node (ref "IC2") (pin "5") (pinfunction "VDD_5") (pintype "bidirectional"))
      (node (ref "IC20") (pin "5") (pinfunction "V+_5") (pintype "power_in"))
      (node (ref "IC21") (pin "5") (pinfunction "VDD_5") (pintype "bidirectional"))
      (node (ref "IC22") (pin "5") (pinfunction "V+_5") (pintype "power_in"))
      (node (ref "IC23") (pin "5") (pinfunction "VDD_5") (pintype "bidirectional"))
      (node (ref "IC24") (pin "5") (pinfunction "V+_5") (pintype "power_in"))
      (node (ref "IC25") (pin "5") (pinfunction "VDD_5") (pintype "bidirectional"))
      (node (ref "IC26") (pin "5") (pinfunction "V+_5") (pintype "power_in"))
      (node (ref "IC27") (pin "5") (pinfunction "VDD_5") (pintype "bidirectional"))
      (node (ref "IC28") (pin "5") (pinfunction "V+_5") (pintype "power_in"))
      (node (ref "IC29") (pin "5") (pinfunction "VDD_5") (pintype "bidirectional"))
      (node (ref "IC3") (pin "5") (pinfunction "V+_5") (pintype "power_in"))
      (node (ref "IC30") (pin "5") (pinfunction "V+_5") (pintype "power_in"))
      (node (ref "IC31") (pin "5") (pinfunction "VDD_5") (pintype "bidirectional"))
      (node (ref "IC32") (pin "5") (pinfunction "V+_5") (pintype "power_in"))
      (node (ref "IC4") (pin "5") (pinfunction "V+_5") (pintype "power_in"))
      (node (ref "IC5") (pin "5") (pinfunction "VDD_5") (pintype "bidirectional"))
      (node (ref "IC6") (pin "5") (pinfunction "V+_5") (pintype "power_in"))
      (node (ref "IC7") (pin "5") (pinfunction "VDD_5") (pintype "bidirectional"))
      (node (ref "IC8") (pin "5") (pinfunction "V+_5") (pintype "power_in"))
      (node (ref "IC9") (pin "5") (pinfunction "VDD_5") (pintype "bidirectional"))
      (node (ref "JP1") (pin "39") (pinfunction "39_39") (pintype "passive"))
      (node (ref "JP1") (pin "40") (pinfunction "40_40") (pintype "passive"))
      (node (ref "U1") (pin "2") (pinfunction "VIN_2") (pintype "input"))
      (node (ref "U10") (pin "2") (pinfunction "VIN_2") (pintype "input"))
      (node (ref "U11") (pin "2") (pinfunction "VIN_2") (pintype "input"))
      (node (ref "U12") (pin "2") (pinfunction "VIN_2") (pintype "input"))
      (node (ref "U13") (pin "2") (pinfunction "VIN_2") (pintype "input"))
      (node (ref "U14") (pin "2") (pinfunction "VIN_2") (pintype "input"))
      (node (ref "U15") (pin "2") (pinfunction "VIN_2") (pintype "input"))
      (node (ref "U16") (pin "2") (pinfunction "VIN_2") (pintype "input"))
      (node (ref "U2") (pin "2") (pinfunction "VIN_2") (pintype "input"))
      (node (ref "U3") (pin "2") (pinfunction "VIN_2") (pintype "input"))
      (node (ref "U4") (pin "2") (pinfunction "VIN_2") (pintype "input"))
      (node (ref "U5") (pin "2") (pinfunction "VIN_2") (pintype "input"))
      (node (ref "U6") (pin "2") (pinfunction "VIN_2") (pintype "input"))
      (node (ref "U7") (pin "2") (pinfunction "VIN_2") (pintype "input"))
      (node (ref "U8") (pin "2") (pinfunction "VIN_2") (pintype "input"))
      (node (ref "U9") (pin "2") (pinfunction "VIN_2") (pintype "input"))
    )
    (net (code "2") (name "+12V") (class "Default")
      (node (ref "JP1") (pin "35") (pinfunction "35_35") (pintype "passive"))
      (node (ref "JP1") (pin "36") (pinfunction "36_36") (pintype "passive"))
    )
    (net (code "3") (name "GND") (class "Default")
      (node (ref "C100") (pin "2") (pinfunction "2_2") (pintype "passive"))
      (node (ref "C101") (pin "2") (pinfunction "2_2") (pintype "passive"))
      (node (ref "C102") (pin "2") (pinfunction "2_2") (pintype "passive"))
      (node (ref "C103") (pin "2") (pinfunction "2_2") (pintype "passive"))
      (node (ref "C104") (pin "2") (pinfunction "2_2") (pintype "passive"))
      (node (ref "C105") (pin "2") (pinfunction "2_2") (pintype "passive"))
      (node (ref "C106") (pin "2") (pinfunction "2_2") (pintype "passive"))
      (node (ref "C107") (pin "2") (pinfunction "2_2") (pintype "passive"))
      (node (ref "C108") (pin "2") (pinfunction "2_2") (pintype "passive"))
      (node (ref "C109") (pin "2") (pinfunction "2_2") (pintype "passive"))
      (node (ref "C11") (pin "2") (pinfunction "2_2") (pintype "passive"))
      (node (ref "C110") (pin "2") (pinfunction "2_2") (pintype "passive"))
      (node (ref "C111") (pin "2") (pinfunction "2_2") (pintype "passive"))
      (node (ref "C112") (pin "2") (pinfunction "2_2") (pintype "passive"))
      (node (ref "C14") (pin "2") (pinfunction "2_2") (pintype "passive"))
      (node (ref "C17") (pin "2") (pinfunction "2_2") (pintype "passive"))
      (node (ref "C2") (pin "2") (pinfunction "2_2") (pintype "passive"))
      (node (ref "C20") (pin "2") (pinfunction "2_2") (pintype "passive"))
      (node (ref "C23") (pin "2") (pinfunction "2_2") (pintype "passive"))
      (node (ref "C26") (pin "2") (pinfunction "2_2") (pintype "passive"))
      (node (ref "C29") (pin "2") (pinfunction "2_2") (pintype "passive"))
      (node (ref "C32") (pin "2") (pinfunction "2_2") (pintype "passive"))
      (node (ref "C35") (pin "2") (pinfunction "2_2") (pintype "passive"))
      (node (ref "C38") (pin "2") (pinfunction "2_2") (pintype "passive"))
      (node (ref "C41") (pin "2") (pinfunction "2_2") (pintype "passive"))
      (node (ref "C44") (pin "2") (pinfunction "2_2") (pintype "passive"))
      (node (ref "C47") (pin "2") (pinfunction "2_2") (pintype "passive"))
      (node (ref "C5") (pin "2") (pinfunction "2_2") (pintype "passive"))
      (node (ref "C8") (pin "2") (pinfunction "2_2") (pintype "passive"))
      (node (ref "C81") (pin "2") (pinfunction "2_2") (pintype "passive"))
      (node (ref "C82") (pin "2") (pinfunction "2_2") (pintype "passive"))
      (node (ref "C83") (pin "2") (pinfunction "2_2") (pintype "passive"))
      (node (ref "C84") (pin "2") (pinfunction "2_2") (pintype "passive"))
      (node (ref "C85") (pin "2") (pinfunction "2_2") (pintype "passive"))
      (node (ref "C86") (pin "2") (pinfunction "2_2") (pintype "passive"))
      (node (ref "C87") (pin "2") (pinfunction "2_2") (pintype "passive"))
      (node (ref "C88") (pin "2") (pinfunction "2_2") (pintype "passive"))
      (node (ref "C89") (pin "2") (pinfunction "2_2") (pintype "passive"))
      (node (ref "C90") (pin "2") (pinfunction "2_2") (pintype "passive"))
      (node (ref "C91") (pin "2") (pinfunction "2_2") (pintype "passive"))
      (node (ref "C92") (pin "2") (pinfunction "2_2") (pintype "passive"))
      (node (ref "C93") (pin "2") (pinfunction "2_2") (pintype "passive"))
      (node (ref "C94") (pin "2") (pinfunction "2_2") (pintype "passive"))
      (node (ref "C95") (pin "2") (pinfunction "2_2") (pintype "passive"))
      (node (ref "C96") (pin "2") (pinfunction "2_2") (pintype "passive"))
      (node (ref "C97") (pin "2") (pinfunction "2_2") (pintype "passive"))
      (node (ref "C98") (pin "2") (pinfunction "2_2") (pintype "passive"))
      (node (ref "C99") (pin "2") (pinfunction "2_2") (pintype "passive"))
      (node (ref "IC1") (pin "2") (pinfunction "GND_2") (pintype "bidirectional"))
      (node (ref "IC10") (pin "2") (pinfunction "V-_2") (pintype "power_in"))
      (node (ref "IC11") (pin "2") (pinfunction "GND_2") (pintype "bidirectional"))
      (node (ref "IC12") (pin "2") (pinfunction "V-_2") (pintype "power_in"))
      (node (ref "IC13") (pin "2") (pinfunction "GND_2") (pintype "bidirectional"))
      (node (ref "IC14") (pin "2") (pinfunction "V-_2") (pintype "power_in"))
      (node (ref "IC15") (pin "2") (pinfunction "GND_2") (pintype "bidirectional"))
      (node (ref "IC16") (pin "2") (pinfunction "V-_2") (pintype "power_in"))
      (node (ref "IC17") (pin "2") (pinfunction "GND_2") (pintype "bidirectional"))
      (node (ref "IC18") (pin "2") (pinfunction "V-_2") (pintype "power_in"))
      (node (ref "IC19") (pin "2") (pinfunction "GND_2") (pintype "bidirectional"))
      (node (ref "IC2") (pin "2") (pinfunction "GND_2") (pintype "bidirectional"))
      (node (ref "IC20") (pin "2") (pinfunction "V-_2") (pintype "power_in"))
      (node (ref "IC21") (pin "2") (pinfunction "GND_2") (pintype "bidirectional"))
      (node (ref "IC22") (pin "2") (pinfunction "V-_2") (pintype "power_in"))
      (node (ref "IC23") (pin "2") (pinfunction "GND_2") (pintype "bidirectional"))
      (node (ref "IC24") (pin "2") (pinfunction "V-_2") (pintype "power_in"))
      (node (ref "IC25") (pin "2") (pinfunction "GND_2") (pintype "bidirectional"))
      (node (ref "IC26") (pin "2") (pinfunction "V-_2") (pintype "power_in"))
      (node (ref "IC27") (pin "2") (pinfunction "GND_2") (pintype "bidirectional"))
      (node (ref "IC28") (pin "2") (pinfunction "V-_2") (pintype "power_in"))
      (node (ref "IC29") (pin "2") (pinfunction "GND_2") (pintype "bidirectional"))
      (node (ref "IC3") (pin "2") (pinfunction "V-_2") (pintype "power_in"))
      (node (ref "IC30") (pin "2") (pinfunction "V-_2") (pintype "power_in"))
      (node (ref "IC31") (pin "2") (pinfunction "GND_2") (pintype "bidirectional"))
      (node (ref "IC32") (pin "2") (pinfunction "V-_2") (pintype "power_in"))
      (node (ref "IC4") (pin "2") (pinfunction "V-_2") (pintype "power_in"))
      (node (ref "IC5") (pin "2") (pinfunction "GND_2") (pintype "bidirectional"))
      (node (ref "IC6") (pin "2") (pinfunction "V-_2") (pintype "power_in"))
      (node (ref "IC7") (pin "2") (pinfunction "GND_2") (pintype "bidirectional"))
      (node (ref "IC8") (pin "2") (pinfunction "V-_2") (pintype "power_in"))
      (node (ref "IC9") (pin "2") (pinfunction "GND_2") (pintype "bidirectional"))
      (node (ref "JP1") (pin "10") (pinfunction "10_10") (pintype "passive"))
      (node (ref "JP1") (pin "12") (pinfunction "12_12") (pintype "passive"))
      (node (ref "JP1") (pin "14") (pinfunction "14_14") (pintype "passive"))
      (node (ref "JP1") (pin "16") (pinfunction "16_16") (pintype "passive"))
      (node (ref "JP1") (pin "18") (pinfunction "18_18") (pintype "passive"))
      (node (ref "JP1") (pin "2") (pinfunction "2_2") (pintype "passive"))
      (node (ref "JP1") (pin "20") (pinfunction "20_20") (pintype "passive"))
      (node (ref "JP1") (pin "22") (pinfunction "22_22") (pintype "passive"))
      (node (ref "JP1") (pin "24") (pinfunction "24_24") (pintype "passive"))
      (node (ref "JP1") (pin "26") (pinfunction "26_26") (pintype "passive"))
      (node (ref "JP1") (pin "28") (pinfunction "28_28") (pintype "passive"))
      (node (ref "JP1") (pin "30") (pinfunction "30_30") (pintype "passive"))
      (node (ref "JP1") (pin "32") (pinfunction "32_32") (pintype "passive"))
      (node (ref "JP1") (pin "33") (pinfunction "33_33") (pintype "passive"))
      (node (ref "JP1") (pin "34") (pinfunction "34_34") (pintype "passive"))
      (node (ref "JP1") (pin "37") (pinfunction "37_37") (pintype "passive"))
      (node (ref "JP1") (pin "38") (pinfunction "38_38") (pintype "passive"))
      (node (ref "JP1") (pin "4") (pinfunction "4_4") (pintype "passive"))
      (node (ref "JP1") (pin "6") (pinfunction "6_6") (pintype "passive"))
      (node (ref "JP1") (pin "8") (pinfunction "8_8") (pintype "passive"))
      (node (ref "U1") (pin "4") (pinfunction "GND_4") (pintype "passive"))
      (node (ref "U10") (pin "4") (pinfunction "GND_4") (pintype "passive"))
      (node (ref "U11") (pin "4") (pinfunction "GND_4") (pintype "passive"))
      (node (ref "U12") (pin "4") (pinfunction "GND_4") (pintype "passive"))
      (node (ref "U13") (pin "4") (pinfunction "GND_4") (pintype "passive"))
      (node (ref "U14") (pin "4") (pinfunction "GND_4") (pintype "passive"))
      (node (ref "U15") (pin "4") (pinfunction "GND_4") (pintype "passive"))
      (node (ref "U16") (pin "4") (pinfunction "GND_4") (pintype "passive"))
      (node (ref "U2") (pin "4") (pinfunction "GND_4") (pintype "passive"))
      (node (ref "U3") (pin "4") (pinfunction "GND_4") (pintype "passive"))
      (node (ref "U4") (pin "4") (pinfunction "GND_4") (pintype "passive"))
      (node (ref "U5") (pin "4") (pinfunction "GND_4") (pintype "passive"))
      (node (ref "U6") (pin "4") (pinfunction "GND_4") (pintype "passive"))
      (node (ref "U7") (pin "4") (pinfunction "GND_4") (pintype "passive"))
      (node (ref "U8") (pin "4") (pinfunction "GND_4") (pintype "passive"))
      (node (ref "U9") (pin "4") (pinfunction "GND_4") (pintype "passive"))
    )
    (net (code "4") (name "INPUT1+") (class "Default")
      (node (ref "C3") (pin "2") (pinfunction "2_2") (pintype "passive"))
      (node (ref "IC3") (pin "1") (pinfunction "OUT_1") (pintype "output"))
      (node (ref "IC3") (pin "4") (pinfunction "-IN_4") (pintype "input"))
      (node (ref "JP1") (pin "1") (pinfunction "1_1") (pintype "passive"))
    )
    (net (code "5") (name "INPUT2+") (class "Default")
      (node (ref "C6") (pin "2") (pinfunction "2_2") (pintype "passive"))
      (node (ref "IC4") (pin "1") (pinfunction "OUT_1") (pintype "output"))
      (node (ref "IC4") (pin "4") (pinfunction "-IN_4") (pintype "input"))
      (node (ref "JP1") (pin "3") (pinfunction "3_3") (pintype "passive"))
    )
    (net (code "6") (name "INPUT3+") (class "Default")
      (node (ref "C9") (pin "2") (pinfunction "2_2") (pintype "passive"))
      (node (ref "IC6") (pin "1") (pinfunction "OUT_1") (pintype "output"))
      (node (ref "IC6") (pin "4") (pinfunction "-IN_4") (pintype "input"))
      (node (ref "JP1") (pin "5") (pinfunction "5_5") (pintype "passive"))
    )
    (net (code "7") (name "INPUT4+") (class "Default")
      (node (ref "C12") (pin "2") (pinfunction "2_2") (pintype "passive"))
      (node (ref "IC8") (pin "1") (pinfunction "OUT_1") (pintype "output"))
      (node (ref "IC8") (pin "4") (pinfunction "-IN_4") (pintype "input"))
      (node (ref "JP1") (pin "7") (pinfunction "7_7") (pintype "passive"))
    )
    (net (code "8") (name "INPUT5+") (class "Default")
      (node (ref "C15") (pin "2") (pinfunction "2_2") (pintype "passive"))
      (node (ref "IC10") (pin "1") (pinfunction "OUT_1") (pintype "output"))
      (node (ref "IC10") (pin "4") (pinfunction "-IN_4") (pintype "input"))
      (node (ref "JP1") (pin "9") (pinfunction "9_9") (pintype "passive"))
    )
    (net (code "9") (name "INPUT6+") (class "Default")
      (node (ref "C18") (pin "2") (pinfunction "2_2") (pintype "passive"))
      (node (ref "IC12") (pin "1") (pinfunction "OUT_1") (pintype "output"))
      (node (ref "IC12") (pin "4") (pinfunction "-IN_4") (pintype "input"))
      (node (ref "JP1") (pin "11") (pinfunction "11_11") (pintype "passive"))
    )
    (net (code "10") (name "INPUT7+") (class "Default")
      (node (ref "C21") (pin "2") (pinfunction "2_2") (pintype "passive"))
      (node (ref "IC14") (pin "1") (pinfunction "OUT_1") (pintype "output"))
      (node (ref "IC14") (pin "4") (pinfunction "-IN_4") (pintype "input"))
      (node (ref "JP1") (pin "13") (pinfunction "13_13") (pintype "passive"))
    )
    (net (code "11") (name "INPUT8+") (class "Default")
      (node (ref "C24") (pin "2") (pinfunction "2_2") (pintype "passive"))
      (node (ref "IC16") (pin "1") (pinfunction "OUT_1") (pintype "output"))
      (node (ref "IC16") (pin "4") (pinfunction "-IN_4") (pintype "input"))
      (node (ref "JP1") (pin "15") (pinfunction "15_15") (pintype "passive"))
    )
    (net (code "12") (name "INPUT9+") (class "Default")
      (node (ref "C27") (pin "2") (pinfunction "2_2") (pintype "passive"))
      (node (ref "IC18") (pin "1") (pinfunction "OUT_1") (pintype "output"))
      (node (ref "IC18") (pin "4") (pinfunction "-IN_4") (pintype "input"))
      (node (ref "JP1") (pin "17") (pinfunction "17_17") (pintype "passive"))
    )
    (net (code "13") (name "INPUT10+") (class "Default")
      (node (ref "C30") (pin "2") (pinfunction "2_2") (pintype "passive"))
      (node (ref "IC20") (pin "1") (pinfunction "OUT_1") (pintype "output"))
      (node (ref "IC20") (pin "4") (pinfunction "-IN_4") (pintype "input"))
      (node (ref "JP1") (pin "19") (pinfunction "19_19") (pintype "passive"))
    )
    (net (code "14") (name "INPUT11+") (class "Default")
      (node (ref "C33") (pin "2") (pinfunction "2_2") (pintype "passive"))
      (node (ref "IC22") (pin "1") (pinfunction "OUT_1") (pintype "output"))
      (node (ref "IC22") (pin "4") (pinfunction "-IN_4") (pintype "input"))
      (node (ref "JP1") (pin "21") (pinfunction "21_21") (pintype "passive"))
    )
    (net (code "15") (name "INPUT12+") (class "Default")
      (node (ref "C36") (pin "2") (pinfunction "2_2") (pintype "passive"))
      (node (ref "IC24") (pin "1") (pinfunction "OUT_1") (pintype "output"))
      (node (ref "IC24") (pin "4") (pinfunction "-IN_4") (pintype "input"))
      (node (ref "JP1") (pin "23") (pinfunction "23_23") (pintype "passive"))
    )
    (net (code "16") (name "INPUT13+") (class "Default")
      (node (ref "C39") (pin "2") (pinfunction "2_2") (pintype "passive"))
      (node (ref "IC26") (pin "1") (pinfunction "OUT_1") (pintype "output"))
      (node (ref "IC26") (pin "4") (pinfunction "-IN_4") (pintype "input"))
      (node (ref "JP1") (pin "25") (pinfunction "25_25") (pintype "passive"))
    )
    (net (code "17") (name "INPUT14+") (class "Default")
      (node (ref "C42") (pin "2") (pinfunction "2_2") (pintype "passive"))
      (node (ref "IC28") (pin "1") (pinfunction "OUT_1") (pintype "output"))
      (node (ref "IC28") (pin "4") (pinfunction "-IN_4") (pintype "input"))
      (node (ref "JP1") (pin "27") (pinfunction "27_27") (pintype "passive"))
    )
    (net (code "18") (name "INPUT15+") (class "Default")
      (node (ref "C45") (pin "2") (pinfunction "2_2") (pintype "passive"))
      (node (ref "IC30") (pin "1") (pinfunction "OUT_1") (pintype "output"))
      (node (ref "IC30") (pin "4") (pinfunction "-IN_4") (pintype "input"))
      (node (ref "JP1") (pin "29") (pinfunction "29_29") (pintype "passive"))
    )
    (net (code "19") (name "INPUT16+") (class "Default")
      (node (ref "C48") (pin "2") (pinfunction "2_2") (pintype "passive"))
      (node (ref "IC32") (pin "1") (pinfunction "OUT_1") (pintype "output"))
      (node (ref "IC32") (pin "4") (pinfunction "-IN_4") (pintype "input"))
      (node (ref "JP1") (pin "31") (pinfunction "31_31") (pintype "passive"))
    )
    (net (code "20") (name "Net-(C3-Pad1)") (class "Default")
      (node (ref "C3") (pin "1") (pinfunction "1_1") (pintype "passive"))
      (node (ref "R2") (pin "1") (pinfunction "1_1") (pintype "passive"))
      (node (ref "R3") (pin "2") (pinfunction "2_2") (pintype "passive"))
    )
    (net (code "21") (name "Net-(C6-Pad1)") (class "Default")
      (node (ref "C6") (pin "1") (pinfunction "1_1") (pintype "passive"))
      (node (ref "R5") (pin "1") (pinfunction "1_1") (pintype "passive"))
      (node (ref "R6") (pin "2") (pinfunction "2_2") (pintype "passive"))
    )
    (net (code "22") (name "Net-(C9-Pad1)") (class "Default")
      (node (ref "C9") (pin "1") (pinfunction "1_1") (pintype "passive"))
      (node (ref "R8") (pin "1") (pinfunction "1_1") (pintype "passive"))
      (node (ref "R9") (pin "2") (pinfunction "2_2") (pintype "passive"))
    )
    (net (code "23") (name "Net-(C12-Pad1)") (class "Default")
      (node (ref "C12") (pin "1") (pinfunction "1_1") (pintype "passive"))
      (node (ref "R11") (pin "1") (pinfunction "1_1") (pintype "passive"))
      (node (ref "R12") (pin "2") (pinfunction "2_2") (pintype "passive"))
    )
    (net (code "24") (name "Net-(C15-Pad1)") (class "Default")
      (node (ref "C15") (pin "1") (pinfunction "1_1") (pintype "passive"))
      (node (ref "R14") (pin "1") (pinfunction "1_1") (pintype "passive"))
      (node (ref "R15") (pin "2") (pinfunction "2_2") (pintype "passive"))
    )
    (net (code "25") (name "Net-(C18-Pad1)") (class "Default")
      (node (ref "C18") (pin "1") (pinfunction "1_1") (pintype "passive"))
      (node (ref "R17") (pin "1") (pinfunction "1_1") (pintype "passive"))
      (node (ref "R18") (pin "2") (pinfunction "2_2") (pintype "passive"))
    )
    (net (code "26") (name "Net-(C21-Pad1)") (class "Default")
      (node (ref "C21") (pin "1") (pinfunction "1_1") (pintype "passive"))
      (node (ref "R20") (pin "1") (pinfunction "1_1") (pintype "passive"))
      (node (ref "R21") (pin "2") (pinfunction "2_2") (pintype "passive"))
    )
    (net (code "27") (name "Net-(C24-Pad1)") (class "Default")
      (node (ref "C24") (pin "1") (pinfunction "1_1") (pintype "passive"))
      (node (ref "R23") (pin "1") (pinfunction "1_1") (pintype "passive"))
      (node (ref "R24") (pin "2") (pinfunction "2_2") (pintype "passive"))
    )
    (net (code "28") (name "Net-(C27-Pad1)") (class "Default")
      (node (ref "C27") (pin "1") (pinfunction "1_1") (pintype "passive"))
      (node (ref "R26") (pin "1") (pinfunction "1_1") (pintype "passive"))
      (node (ref "R27") (pin "2") (pinfunction "2_2") (pintype "passive"))
    )
    (net (code "29") (name "Net-(C30-Pad1)") (class "Default")
      (node (ref "C30") (pin "1") (pinfunction "1_1") (pintype "passive"))
      (node (ref "R29") (pin "1") (pinfunction "1_1") (pintype "passive"))
      (node (ref "R30") (pin "2") (pinfunction "2_2") (pintype "passive"))
    )
    (net (code "30") (name "Net-(C33-Pad1)") (class "Default")
      (node (ref "C33") (pin "1") (pinfunction "1_1") (pintype "passive"))
      (node (ref "R32") (pin "1") (pinfunction "1_1") (pintype "passive"))
      (node (ref "R33") (pin "2") (pinfunction "2_2") (pintype "passive"))
    )
    (net (code "31") (name "Net-(C36-Pad1)") (class "Default")
      (node (ref "C36") (pin "1") (pinfunction "1_1") (pintype "passive"))
      (node (ref "R35") (pin "1") (pinfunction "1_1") (pintype "passive"))
      (node (ref "R36") (pin "2") (pinfunction "2_2") (pintype "passive"))
    )
    (net (code "32") (name "Net-(C39-Pad1)") (class "Default")
      (node (ref "C39") (pin "1") (pinfunction "1_1") (pintype "passive"))
      (node (ref "R38") (pin "1") (pinfunction "1_1") (pintype "passive"))
      (node (ref "R39") (pin "2") (pinfunction "2_2") (pintype "passive"))
    )
    (net (code "33") (name "Net-(C42-Pad1)") (class "Default")
      (node (ref "C42") (pin "1") (pinfunction "1_1") (pintype "passive"))
      (node (ref "R41") (pin "1") (pinfunction "1_1") (pintype "passive"))
      (node (ref "R42") (pin "2") (pinfunction "2_2") (pintype "passive"))
    )
    (net (code "34") (name "Net-(C45-Pad1)") (class "Default")
      (node (ref "C45") (pin "1") (pinfunction "1_1") (pintype "passive"))
      (node (ref "R44") (pin "1") (pinfunction "1_1") (pintype "passive"))
      (node (ref "R45") (pin "2") (pinfunction "2_2") (pintype "passive"))
    )
    (net (code "35") (name "Net-(C48-Pad1)") (class "Default")
      (node (ref "C48") (pin "1") (pinfunction "1_1") (pintype "passive"))
      (node (ref "R47") (pin "1") (pinfunction "1_1") (pintype "passive"))
      (node (ref "R48") (pin "2") (pinfunction "2_2") (pintype "passive"))
    )
    (net (code "36") (name "Net-(IC1-IN-)") (class "Default")
      (node (ref "C1") (pin "1") (pinfunction "1_1") (pintype "passive"))
      (node (ref "C49") (pin "1") (pinfunction "1_1") (pintype "passive"))
      (node (ref "C50") (pin "1") (pinfunction "1_1") (pintype "passive"))
      (node (ref "IC1") (pin "4") (pinfunction "IN-_4") (pintype "bidirectional"))
      (node (ref "R1") (pin "1") (pinfunction "1_1") (pintype "passive"))
      (node (ref "R49") (pin "2") (pinfunction "2_2") (pintype "passive"))
    )
    (net (code "37") (name "Net-(IC1-OUT)") (class "Default")
      (node (ref "C1") (pin "2") (pinfunction "2_2") (pintype "passive"))
      (node (ref "C49") (pin "2") (pinfunction "2_2") (pintype "passive"))
      (node (ref "C50") (pin "2") (pinfunction "2_2") (pintype "passive"))
      (node (ref "IC1") (pin "1") (pinfunction "OUT_1") (pintype "bidirectional"))
      (node (ref "R1") (pin "2") (pinfunction "2_2") (pintype "passive"))
      (node (ref "R3") (pin "1") (pinfunction "1_1") (pintype "passive"))
    )
    (net (code "38") (name "Net-(IC2-IN-)") (class "Default")
      (node (ref "C4") (pin "1") (pinfunction "1_1") (pintype "passive"))
      (node (ref "C51") (pin "1") (pinfunction "1_1") (pintype "passive"))
      (node (ref "C52") (pin "1") (pinfunction "1_1") (pintype "passive"))
      (node (ref "IC2") (pin "4") (pinfunction "IN-_4") (pintype "bidirectional"))
      (node (ref "R4") (pin "1") (pinfunction "1_1") (pintype "passive"))
      (node (ref "R50") (pin "2") (pinfunction "2_2") (pintype "passive"))
    )
    (net (code "39") (name "Net-(IC2-OUT)") (class "Default")
      (node (ref "C4") (pin "2") (pinfunction "2_2") (pintype "passive"))
      (node (ref "C51") (pin "2") (pinfunction "2_2") (pintype "passive"))
      (node (ref "C52") (pin "2") (pinfunction "2_2") (pintype "passive"))
      (node (ref "IC2") (pin "1") (pinfunction "OUT_1") (pintype "bidirectional"))
      (node (ref "R4") (pin "2") (pinfunction "2_2") (pintype "passive"))
      (node (ref "R6") (pin "1") (pinfunction "1_1") (pintype "passive"))
    )
    (net (code "40") (name "Net-(IC3-+IN)") (class "Default")
      (node (ref "C2") (pin "1") (pinfunction "1_1") (pintype "passive"))
      (node (ref "IC3") (pin "3") (pinfunction "+IN_3") (pintype "input"))
      (node (ref "R2") (pin "2") (pinfunction "2_2") (pintype "passive"))
    )
    (net (code "41") (name "Net-(IC4-+IN)") (class "Default")
      (node (ref "C5") (pin "1") (pinfunction "1_1") (pintype "passive"))
      (node (ref "IC4") (pin "3") (pinfunction "+IN_3") (pintype "input"))
      (node (ref "R5") (pin "2") (pinfunction "2_2") (pintype "passive"))
    )
    (net (code "42") (name "Net-(IC5-IN-)") (class "Default")
      (node (ref "C53") (pin "1") (pinfunction "1_1") (pintype "passive"))
      (node (ref "C54") (pin "1") (pinfunction "1_1") (pintype "passive"))
      (node (ref "C7") (pin "1") (pinfunction "1_1") (pintype "passive"))
      (node (ref "IC5") (pin "4") (pinfunction "IN-_4") (pintype "bidirectional"))
      (node (ref "R51") (pin "2") (pinfunction "2_2") (pintype "passive"))
      (node (ref "R7") (pin "1") (pinfunction "1_1") (pintype "passive"))
    )
    (net (code "43") (name "Net-(IC5-OUT)") (class "Default")
      (node (ref "C53") (pin "2") (pinfunction "2_2") (pintype "passive"))
      (node (ref "C54") (pin "2") (pinfunction "2_2") (pintype "passive"))
      (node (ref "C7") (pin "2") (pinfunction "2_2") (pintype "passive"))
      (node (ref "IC5") (pin "1") (pinfunction "OUT_1") (pintype "bidirectional"))
      (node (ref "R7") (pin "2") (pinfunction "2_2") (pintype "passive"))
      (node (ref "R9") (pin "1") (pinfunction "1_1") (pintype "passive"))
    )
    (net (code "44") (name "Net-(IC6-+IN)") (class "Default")
      (node (ref "C8") (pin "1") (pinfunction "1_1") (pintype "passive"))
      (node (ref "IC6") (pin "3") (pinfunction "+IN_3") (pintype "input"))
      (node (ref "R8") (pin "2") (pinfunction "2_2") (pintype "passive"))
    )
    (net (code "45") (name "Net-(IC7-IN-)") (class "Default")
      (node (ref "C10") (pin "1") (pinfunction "1_1") (pintype "passive"))
      (node (ref "C55") (pin "1") (pinfunction "1_1") (pintype "passive"))
      (node (ref "C56") (pin "1") (pinfunction "1_1") (pintype "passive"))
      (node (ref "IC7") (pin "4") (pinfunction "IN-_4") (pintype "bidirectional"))
      (node (ref "R10") (pin "1") (pinfunction "1_1") (pintype "passive"))
      (node (ref "R52") (pin "2") (pinfunction "2_2") (pintype "passive"))
    )
    (net (code "46") (name "Net-(IC7-OUT)") (class "Default")
      (node (ref "C10") (pin "2") (pinfunction "2_2") (pintype "passive"))
      (node (ref "C55") (pin "2") (pinfunction "2_2") (pintype "passive"))
      (node (ref "C56") (pin "2") (pinfunction "2_2") (pintype "passive"))
      (node (ref "IC7") (pin "1") (pinfunction "OUT_1") (pintype "bidirectional"))
      (node (ref "R10") (pin "2") (pinfunction "2_2") (pintype "passive"))
      (node (ref "R12") (pin "1") (pinfunction "1_1") (pintype "passive"))
    )
    (net (code "47") (name "Net-(IC8-+IN)") (class "Default")
      (node (ref "C11") (pin "1") (pinfunction "1_1") (pintype "passive"))
      (node (ref "IC8") (pin "3") (pinfunction "+IN_3") (pintype "input"))
      (node (ref "R11") (pin "2") (pinfunction "2_2") (pintype "passive"))
    )
    (net (code "48") (name "Net-(IC9-IN-)") (class "Default")
      (node (ref "C13") (pin "1") (pinfunction "1_1") (pintype "passive"))
      (node (ref "C57") (pin "1") (pinfunction "1_1") (pintype "passive"))
      (node (ref "C58") (pin "1") (pinfunction "1_1") (pintype "passive"))
      (node (ref "IC9") (pin "4") (pinfunction "IN-_4") (pintype "bidirectional"))
      (node (ref "R13") (pin "1") (pinfunction "1_1") (pintype "passive"))
      (node (ref "R53") (pin "2") (pinfunction "2_2") (pintype "passive"))
    )
    (net (code "49") (name "Net-(IC9-OUT)") (class "Default")
      (node (ref "C13") (pin "2") (pinfunction "2_2") (pintype "passive"))
      (node (ref "C57") (pin "2") (pinfunction "2_2") (pintype "passive"))
      (node (ref "C58") (pin "2") (pinfunction "2_2") (pintype "passive"))
      (node (ref "IC9") (pin "1") (pinfunction "OUT_1") (pintype "bidirectional"))
      (node (ref "R13") (pin "2") (pinfunction "2_2") (pintype "passive"))
      (node (ref "R15") (pin "1") (pinfunction "1_1") (pintype "passive"))
    )
    (net (code "50") (name "Net-(IC10-+IN)") (class "Default")
      (node (ref "C14") (pin "1") (pinfunction "1_1") (pintype "passive"))
      (node (ref "IC10") (pin "3") (pinfunction "+IN_3") (pintype "input"))
      (node (ref "R14") (pin "2") (pinfunction "2_2") (pintype "passive"))
    )
    (net (code "51") (name "Net-(IC11-IN-)") (class "Default")
      (node (ref "C16") (pin "1") (pinfunction "1_1") (pintype "passive"))
      (node (ref "C59") (pin "1") (pinfunction "1_1") (pintype "passive"))
      (node (ref "C60") (pin "1") (pinfunction "1_1") (pintype "passive"))
      (node (ref "IC11") (pin "4") (pinfunction "IN-_4") (pintype "bidirectional"))
      (node (ref "R16") (pin "1") (pinfunction "1_1") (pintype "passive"))
      (node (ref "R54") (pin "2") (pinfunction "2_2") (pintype "passive"))
    )
    (net (code "52") (name "Net-(IC11-OUT)") (class "Default")
      (node (ref "C16") (pin "2") (pinfunction "2_2") (pintype "passive"))
      (node (ref "C59") (pin "2") (pinfunction "2_2") (pintype "passive"))
      (node (ref "C60") (pin "2") (pinfunction "2_2") (pintype "passive"))
      (node (ref "IC11") (pin "1") (pinfunction "OUT_1") (pintype "bidirectional"))
      (node (ref "R16") (pin "2") (pinfunction "2_2") (pintype "passive"))
      (node (ref "R18") (pin "1") (pinfunction "1_1") (pintype "passive"))
    )
    (net (code "53") (name "Net-(IC12-+IN)") (class "Default")
      (node (ref "C17") (pin "1") (pinfunction "1_1") (pintype "passive"))
      (node (ref "IC12") (pin "3") (pinfunction "+IN_3") (pintype "input"))
      (node (ref "R17") (pin "2") (pinfunction "2_2") (pintype "passive"))
    )
    (net (code "54") (name "Net-(IC13-IN-)") (class "Default")
      (node (ref "C19") (pin "1") (pinfunction "1_1") (pintype "passive"))
      (node (ref "C63") (pin "1") (pinfunction "1_1") (pintype "passive"))
      (node (ref "C64") (pin "1") (pinfunction "1_1") (pintype "passive"))
      (node (ref "IC13") (pin "4") (pinfunction "IN-_4") (pintype "bidirectional"))
      (node (ref "R19") (pin "1") (pinfunction "1_1") (pintype "passive"))
      (node (ref "R55") (pin "2") (pinfunction "2_2") (pintype "passive"))
    )
    (net (code "55") (name "Net-(IC13-OUT)") (class "Default")
      (node (ref "C19") (pin "2") (pinfunction "2_2") (pintype "passive"))
      (node (ref "C63") (pin "2") (pinfunction "2_2") (pintype "passive"))
      (node (ref "C64") (pin "2") (pinfunction "2_2") (pintype "passive"))
      (node (ref "IC13") (pin "1") (pinfunction "OUT_1") (pintype "bidirectional"))
      (node (ref "R19") (pin "2") (pinfunction "2_2") (pintype "passive"))
      (node (ref "R21") (pin "1") (pinfunction "1_1") (pintype "passive"))
    )
    (net (code "56") (name "Net-(IC14-+IN)") (class "Default")
      (node (ref "C20") (pin "1") (pinfunction "1_1") (pintype "passive"))
      (node (ref "IC14") (pin "3") (pinfunction "+IN_3") (pintype "input"))
      (node (ref "R20") (pin "2") (pinfunction "2_2") (pintype "passive"))
    )
    (net (code "57") (name "Net-(IC15-IN-)") (class "Default")
      (node (ref "C22") (pin "1") (pinfunction "1_1") (pintype "passive"))
      (node (ref "C61") (pin "1") (pinfunction "1_1") (pintype "passive"))
      (node (ref "C62") (pin "1") (pinfunction "1_1") (pintype "passive"))
      (node (ref "IC15") (pin "4") (pinfunction "IN-_4") (pintype "bidirectional"))
      (node (ref "R22") (pin "1") (pinfunction "1_1") (pintype "passive"))
      (node (ref "R56") (pin "2") (pinfunction "2_2") (pintype "passive"))
    )
    (net (code "58") (name "Net-(IC15-OUT)") (class "Default")
      (node (ref "C22") (pin "2") (pinfunction "2_2") (pintype "passive"))
      (node (ref "C61") (pin "2") (pinfunction "2_2") (pintype "passive"))
      (node (ref "C62") (pin "2") (pinfunction "2_2") (pintype "passive"))
      (node (ref "IC15") (pin "1") (pinfunction "OUT_1") (pintype "bidirectional"))
      (node (ref "R22") (pin "2") (pinfunction "2_2") (pintype "passive"))
      (node (ref "R24") (pin "1") (pinfunction "1_1") (pintype "passive"))
    )
    (net (code "59") (name "Net-(IC16-+IN)") (class "Default")
      (node (ref "C23") (pin "1") (pinfunction "1_1") (pintype "passive"))
      (node (ref "IC16") (pin "3") (pinfunction "+IN_3") (pintype "input"))
      (node (ref "R23") (pin "2") (pinfunction "2_2") (pintype "passive"))
    )
    (net (code "60") (name "Net-(IC17-IN-)") (class "Default")
      (node (ref "C25") (pin "1") (pinfunction "1_1") (pintype "passive"))
      (node (ref "C67") (pin "1") (pinfunction "1_1") (pintype "passive"))
      (node (ref "C68") (pin "1") (pinfunction "1_1") (pintype "passive"))
      (node (ref "IC17") (pin "4") (pinfunction "IN-_4") (pintype "bidirectional"))
      (node (ref "R25") (pin "1") (pinfunction "1_1") (pintype "passive"))
      (node (ref "R58") (pin "2") (pinfunction "2_2") (pintype "passive"))
    )
    (net (code "61") (name "Net-(IC17-OUT)") (class "Default")
      (node (ref "C25") (pin "2") (pinfunction "2_2") (pintype "passive"))
      (node (ref "C67") (pin "2") (pinfunction "2_2") (pintype "passive"))
      (node (ref "C68") (pin "2") (pinfunction "2_2") (pintype "passive"))
      (node (ref "IC17") (pin "1") (pinfunction "OUT_1") (pintype "bidirectional"))
      (node (ref "R25") (pin "2") (pinfunction "2_2") (pintype "passive"))
      (node (ref "R27") (pin "1") (pinfunction "1_1") (pintype "passive"))
    )
    (net (code "62") (name "Net-(IC18-+IN)") (class "Default")
      (node (ref "C26") (pin "1") (pinfunction "1_1") (pintype "passive"))
      (node (ref "IC18") (pin "3") (pinfunction "+IN_3") (pintype "input"))
      (node (ref "R26") (pin "2") (pinfunction "2_2") (pintype "passive"))
    )
    (net (code "63") (name "Net-(IC19-IN-)") (class "Default")
      (node (ref "C28") (pin "1") (pinfunction "1_1") (pintype "passive"))
      (node (ref "C65") (pin "1") (pinfunction "1_1") (pintype "passive"))
      (node (ref "C66") (pin "1") (pinfunction "1_1") (pintype "passive"))
      (node (ref "IC19") (pin "4") (pinfunction "IN-_4") (pintype "bidirectional"))
      (node (ref "R28") (pin "1") (pinfunction "1_1") (pintype "passive"))
      (node (ref "R57") (pin "2") (pinfunction "2_2") (pintype "passive"))
    )
    (net (code "64") (name "Net-(IC19-OUT)") (class "Default")
      (node (ref "C28") (pin "2") (pinfunction "2_2") (pintype "passive"))
      (node (ref "C65") (pin "2") (pinfunction "2_2") (pintype "passive"))
      (node (ref "C66") (pin "2") (pinfunction "2_2") (pintype "passive"))
      (node (ref "IC19") (pin "1") (pinfunction "OUT_1") (pintype "bidirectional"))
      (node (ref "R28") (pin "2") (pinfunction "2_2") (pintype "passive"))
      (node (ref "R30") (pin "1") (pinfunction "1_1") (pintype "passive"))
    )
    (net (code "65") (name "Net-(IC20-+IN)") (class "Default")
      (node (ref "C29") (pin "1") (pinfunction "1_1") (pintype "passive"))
      (node (ref "IC20") (pin "3") (pinfunction "+IN_3") (pintype "input"))
      (node (ref "R29") (pin "2") (pinfunction "2_2") (pintype "passive"))
    )
    (net (code "66") (name "Net-(IC21-IN-)") (class "Default")
      (node (ref "C31") (pin "1") (pinfunction "1_1") (pintype "passive"))
      (node (ref "C69") (pin "1") (pinfunction "1_1") (pintype "passive"))
      (node (ref "C70") (pin "1") (pinfunction "1_1") (pintype "passive"))
      (node (ref "IC21") (pin "4") (pinfunction "IN-_4") (pintype "bidirectional"))
      (node (ref "R31") (pin "1") (pinfunction "1_1") (pintype "passive"))
      (node (ref "R59") (pin "2") (pinfunction "2_2") (pintype "passive"))
    )
    (net (code "67") (name "Net-(IC21-OUT)") (class "Default")
      (node (ref "C31") (pin "2") (pinfunction "2_2") (pintype "passive"))
      (node (ref "C69") (pin "2") (pinfunction "2_2") (pintype "passive"))
      (node (ref "C70") (pin "2") (pinfunction "2_2") (pintype "passive"))
      (node (ref "IC21") (pin "1") (pinfunction "OUT_1") (pintype "bidirectional"))
      (node (ref "R31") (pin "2") (pinfunction "2_2") (pintype "passive"))
      (node (ref "R33") (pin "1") (pinfunction "1_1") (pintype "passive"))
    )
    (net (code "68") (name "Net-(IC22-+IN)") (class "Default")
      (node (ref "C32") (pin "1") (pinfunction "1_1") (pintype "passive"))
      (node (ref "IC22") (pin "3") (pinfunction "+IN_3") (pintype "input"))
      (node (ref "R32") (pin "2") (pinfunction "2_2") (pintype "passive"))
    )
    (net (code "69") (name "Net-(IC23-IN-)") (class "Default")
      (node (ref "C34") (pin "1") (pinfunction "1_1") (pintype "passive"))
      (node (ref "C71") (pin "1") (pinfunction "1_1") (pintype "passive"))
      (node (ref "C72") (pin "1") (pinfunction "1_1") (pintype "passive"))
      (node (ref "IC23") (pin "4") (pinfunction "IN-_4") (pintype "bidirectional"))
      (node (ref "R34") (pin "1") (pinfunction "1_1") (pintype "passive"))
      (node (ref "R60") (pin "2") (pinfunction "2_2") (pintype "passive"))
    )
    (net (code "70") (name "Net-(IC23-OUT)") (class "Default")
      (node (ref "C34") (pin "2") (pinfunction "2_2") (pintype "passive"))
      (node (ref "C71") (pin "2") (pinfunction "2_2") (pintype "passive"))
      (node (ref "C72") (pin "2") (pinfunction "2_2") (pintype "passive"))
      (node (ref "IC23") (pin "1") (pinfunction "OUT_1") (pintype "bidirectional"))
      (node (ref "R34") (pin "2") (pinfunction "2_2") (pintype "passive"))
      (node (ref "R36") (pin "1") (pinfunction "1_1") (pintype "passive"))
    )
    (net (code "71") (name "Net-(IC24-+IN)") (class "Default")
      (node (ref "C35") (pin "1") (pinfunction "1_1") (pintype "passive"))
      (node (ref "IC24") (pin "3") (pinfunction "+IN_3") (pintype "input"))
      (node (ref "R35") (pin "2") (pinfunction "2_2") (pintype "passive"))
    )
    (net (code "72") (name "Net-(IC25-IN-)") (class "Default")
      (node (ref "C37") (pin "1") (pinfunction "1_1") (pintype "passive"))
      (node (ref "C75") (pin "1") (pinfunction "1_1") (pintype "passive"))
      (node (ref "C76") (pin "1") (pinfunction "1_1") (pintype "passive"))
      (node (ref "IC25") (pin "4") (pinfunction "IN-_4") (pintype "bidirectional"))
      (node (ref "R37") (pin "1") (pinfunction "1_1") (pintype "passive"))
      (node (ref "R62") (pin "2") (pinfunction "2_2") (pintype "passive"))
    )
    (net (code "73") (name "Net-(IC25-OUT)") (class "Default")
      (node (ref "C37") (pin "2") (pinfunction "2_2") (pintype "passive"))
      (node (ref "C75") (pin "2") (pinfunction "2_2") (pintype "passive"))
      (node (ref "C76") (pin "2") (pinfunction "2_2") (pintype "passive"))
      (node (ref "IC25") (pin "1") (pinfunction "OUT_1") (pintype "bidirectional"))
      (node (ref "R37") (pin "2") (pinfunction "2_2") (pintype "passive"))
      (node (ref "R39") (pin "1") (pinfunction "1_1") (pintype "passive"))
    )
    (net (code "74") (name "Net-(IC26-+IN)") (class "Default")
      (node (ref "C38") (pin "1") (pinfunction "1_1") (pintype "passive"))
      (node (ref "IC26") (pin "3") (pinfunction "+IN_3") (pintype "input"))
      (node (ref "R38") (pin "2") (pinfunction "2_2") (pintype "passive"))
    )
    (net (code "75") (name "Net-(IC27-IN-)") (class "Default")
      (node (ref "C40") (pin "1") (pinfunction "1_1") (pintype "passive"))
      (node (ref "C73") (pin "1") (pinfunction "1_1") (pintype "passive"))
      (node (ref "C74") (pin "1") (pinfunction "1_1") (pintype "passive"))
      (node (ref "IC27") (pin "4") (pinfunction "IN-_4") (pintype "bidirectional"))
      (node (ref "R40") (pin "1") (pinfunction "1_1") (pintype "passive"))
      (node (ref "R61") (pin "2") (pinfunction "2_2") (pintype "passive"))
    )
    (net (code "76") (name "Net-(IC27-OUT)") (class "Default")
      (node (ref "C40") (pin "2") (pinfunction "2_2") (pintype "passive"))
      (node (ref "C73") (pin "2") (pinfunction "2_2") (pintype "passive"))
      (node (ref "C74") (pin "2") (pinfunction "2_2") (pintype "passive"))
      (node (ref "IC27") (pin "1") (pinfunction "OUT_1") (pintype "bidirectional"))
      (node (ref "R40") (pin "2") (pinfunction "2_2") (pintype "passive"))
      (node (ref "R42") (pin "1") (pinfunction "1_1") (pintype "passive"))
    )
    (net (code "77") (name "Net-(IC28-+IN)") (class "Default")
      (node (ref "C41") (pin "1") (pinfunction "1_1") (pintype "passive"))
      (node (ref "IC28") (pin "3") (pinfunction "+IN_3") (pintype "input"))
      (node (ref "R41") (pin "2") (pinfunction "2_2") (pintype "passive"))
    )
    (net (code "78") (name "Net-(IC29-IN-)") (class "Default")
      (node (ref "C43") (pin "1") (pinfunction "1_1") (pintype "passive"))
      (node (ref "C79") (pin "1") (pinfunction "1_1") (pintype "passive"))
      (node (ref "C80") (pin "1") (pinfunction "1_1") (pintype "passive"))
      (node (ref "IC29") (pin "4") (pinfunction "IN-_4") (pintype "bidirectional"))
      (node (ref "R43") (pin "1") (pinfunction "1_1") (pintype "passive"))
      (node (ref "R64") (pin "2") (pinfunction "2_2") (pintype "passive"))
    )
    (net (code "79") (name "Net-(IC29-OUT)") (class "Default")
      (node (ref "C43") (pin "2") (pinfunction "2_2") (pintype "passive"))
      (node (ref "C79") (pin "2") (pinfunction "2_2") (pintype "passive"))
      (node (ref "C80") (pin "2") (pinfunction "2_2") (pintype "passive"))
      (node (ref "IC29") (pin "1") (pinfunction "OUT_1") (pintype "bidirectional"))
      (node (ref "R43") (pin "2") (pinfunction "2_2") (pintype "passive"))
      (node (ref "R45") (pin "1") (pinfunction "1_1") (pintype "passive"))
    )
    (net (code "80") (name "Net-(IC30-+IN)") (class "Default")
      (node (ref "C44") (pin "1") (pinfunction "1_1") (pintype "passive"))
      (node (ref "IC30") (pin "3") (pinfunction "+IN_3") (pintype "input"))
      (node (ref "R44") (pin "2") (pinfunction "2_2") (pintype "passive"))
    )
    (net (code "81") (name "Net-(IC31-IN-)") (class "Default")
      (node (ref "C46") (pin "1") (pinfunction "1_1") (pintype "passive"))
      (node (ref "C77") (pin "1") (pinfunction "1_1") (pintype "passive"))
      (node (ref "C78") (pin "1") (pinfunction "1_1") (pintype "passive"))
      (node (ref "IC31") (pin "4") (pinfunction "IN-_4") (pintype "bidirectional"))
      (node (ref "R46") (pin "1") (pinfunction "1_1") (pintype "passive"))
      (node (ref "R63") (pin "2") (pinfunction "2_2") (pintype "passive"))
    )
    (net (code "82") (name "Net-(IC31-OUT)") (class "Default")
      (node (ref "C46") (pin "2") (pinfunction "2_2") (pintype "passive"))
      (node (ref "C77") (pin "2") (pinfunction "2_2") (pintype "passive"))
      (node (ref "C78") (pin "2") (pinfunction "2_2") (pintype "passive"))
      (node (ref "IC31") (pin "1") (pinfunction "OUT_1") (pintype "bidirectional"))
      (node (ref "R46") (pin "2") (pinfunction "2_2") (pintype "passive"))
      (node (ref "R48") (pin "1") (pinfunction "1_1") (pintype "passive"))
    )
    (net (code "83") (name "Net-(IC32-+IN)") (class "Default")
      (node (ref "C47") (pin "1") (pinfunction "1_1") (pintype "passive"))
      (node (ref "IC32") (pin "3") (pinfunction "+IN_3") (pintype "input"))
      (node (ref "R47") (pin "2") (pinfunction "2_2") (pintype "passive"))
    )
    (net (code "84") (name "REF_S1") (class "Default")
      (node (ref "C82") (pin "1") (pinfunction "1_1") (pintype "passive"))
      (node (ref "IC1") (pin "3") (pinfunction "IN+_3") (pintype "bidirectional"))
      (node (ref "J1") (pin "2") (pinfunction "2_2") (pintype "bidirectional"))
      (node (ref "U1") (pin "6") (pinfunction "VOUT_6") (pintype "output"))
    )
    (net (code "85") (name "REF_S2") (class "Default")
      (node (ref "C84") (pin "1") (pinfunction "1_1") (pintype "passive"))
      (node (ref "IC2") (pin "3") (pinfunction "IN+_3") (pintype "bidirectional"))
      (node (ref "J1") (pin "4") (pinfunction "4_4") (pintype "bidirectional"))
      (node (ref "U2") (pin "6") (pinfunction "VOUT_6") (pintype "output"))
    )
    (net (code "86") (name "REF_S3") (class "Default")
      (node (ref "C86") (pin "1") (pinfunction "1_1") (pintype "passive"))
      (node (ref "IC5") (pin "3") (pinfunction "IN+_3") (pintype "bidirectional"))
      (node (ref "J1") (pin "6") (pinfunction "6_6") (pintype "bidirectional"))
      (node (ref "U3") (pin "6") (pinfunction "VOUT_6") (pintype "output"))
    )
    (net (code "87") (name "REF_S4") (class "Default")
      (node (ref "C88") (pin "1") (pinfunction "1_1") (pintype "passive"))
      (node (ref "IC7") (pin "3") (pinfunction "IN+_3") (pintype "bidirectional"))
      (node (ref "J1") (pin "8") (pinfunction "8_8") (pintype "bidirectional"))
      (node (ref "U4") (pin "6") (pinfunction "VOUT_6") (pintype "output"))
    )
    (net (code "88") (name "REF_S5") (class "Default")
      (node (ref "C90") (pin "1") (pinfunction "1_1") (pintype "passive"))
      (node (ref "IC9") (pin "3") (pinfunction "IN+_3") (pintype "bidirectional"))
      (node (ref "J2") (pin "2") (pinfunction "2_2") (pintype "bidirectional"))
      (node (ref "U5") (pin "6") (pinfunction "VOUT_6") (pintype "output"))
    )
    (net (code "89") (name "REF_S6") (class "Default")
      (node (ref "C92") (pin "1") (pinfunction "1_1") (pintype "passive"))
      (node (ref "IC11") (pin "3") (pinfunction "IN+_3") (pintype "bidirectional"))
      (node (ref "J2") (pin "4") (pinfunction "4_4") (pintype "bidirectional"))
      (node (ref "U6") (pin "6") (pinfunction "VOUT_6") (pintype "output"))
    )
    (net (code "90") (name "REF_S7") (class "Default")
      (node (ref "C94") (pin "1") (pinfunction "1_1") (pintype "passive"))
      (node (ref "IC13") (pin "3") (pinfunction "IN+_3") (pintype "bidirectional"))
      (node (ref "J2") (pin "6") (pinfunction "6_6") (pintype "bidirectional"))
      (node (ref "U7") (pin "6") (pinfunction "VOUT_6") (pintype "output"))
    )
    (net (code "91") (name "REF_S8") (class "Default")
      (node (ref "C96") (pin "1") (pinfunction "1_1") (pintype "passive"))
      (node (ref "IC15") (pin "3") (pinfunction "IN+_3") (pintype "bidirectional"))
      (node (ref "J2") (pin "8") (pinfunction "8_8") (pintype "bidirectional"))
      (node (ref "U8") (pin "6") (pinfunction "VOUT_6") (pintype "output"))
    )
    (net (code "92") (name "REF_S9") (class "Default")
      (node (ref "C98") (pin "1") (pinfunction "1_1") (pintype "passive"))
      (node (ref "IC17") (pin "3") (pinfunction "IN+_3") (pintype "bidirectional"))
      (node (ref "J3") (pin "2") (pinfunction "2_2") (pintype "bidirectional"))
      (node (ref "U9") (pin "6") (pinfunction "VOUT_6") (pintype "output"))
    )
    (net (code "93") (name "REF_S10") (class "Default")
      (node (ref "C100") (pin "1") (pinfunction "1_1") (pintype "passive"))
      (node (ref "IC19") (pin "3") (pinfunction "IN+_3") (pintype "bidirectional"))
      (node (ref "J3") (pin "4") (pinfunction "4_4") (pintype "bidirectional"))
      (node (ref "U10") (pin "6") (pinfunction "VOUT_6") (pintype "output"))
    )
    (net (code "94") (name "REF_S11") (class "Default")
      (node (ref "C102") (pin "1") (pinfunction "1_1") (pintype "passive"))
      (node (ref "IC21") (pin "3") (pinfunction "IN+_3") (pintype "bidirectional"))
      (node (ref "J3") (pin "6") (pinfunction "6_6") (pintype "bidirectional"))
      (node (ref "U11") (pin "6") (pinfunction "VOUT_6") (pintype "output"))
    )
    (net (code "95") (name "REF_S12") (class "Default")
      (node (ref "C104") (pin "1") (pinfunction "1_1") (pintype "passive"))
      (node (ref "IC23") (pin "3") (pinfunction "IN+_3") (pintype "bidirectional"))
      (node (ref "J3") (pin "8") (pinfunction "8_8") (pintype "bidirectional"))
      (node (ref "U12") (pin "6") (pinfunction "VOUT_6") (pintype "output"))
    )
    (net (code "96") (name "REF_S13") (class "Default")
      (node (ref "C106") (pin "1") (pinfunction "1_1") (pintype "passive"))
      (node (ref "IC25") (pin "3") (pinfunction "IN+_3") (pintype "bidirectional"))
      (node (ref "J4") (pin "2") (pinfunction "2_2") (pintype "bidirectional"))
      (node (ref "U13") (pin "6") (pinfunction "VOUT_6") (pintype "output"))
    )
    (net (code "97") (name "REF_S14") (class "Default")
      (node (ref "C108") (pin "1") (pinfunction "1_1") (pintype "passive"))
      (node (ref "IC27") (pin "3") (pinfunction "IN+_3") (pintype "bidirectional"))
      (node (ref "J4") (pin "4") (pinfunction "4_4") (pintype "bidirectional"))
      (node (ref "U14") (pin "6") (pinfunction "VOUT_6") (pintype "output"))
    )
    (net (code "98") (name "REF_S15") (class "Default")
      (node (ref "C110") (pin "1") (pinfunction "1_1") (pintype "passive"))
      (node (ref "IC29") (pin "3") (pinfunction "IN+_3") (pintype "bidirectional"))
      (node (ref "J4") (pin "6") (pinfunction "6_6") (pintype "bidirectional"))
      (node (ref "U15") (pin "6") (pinfunction "VOUT_6") (pintype "output"))
    )
    (net (code "99") (name "REF_S16") (class "Default")
      (node (ref "C112") (pin "1") (pinfunction "1_1") (pintype "passive"))
      (node (ref "IC31") (pin "3") (pinfunction "IN+_3") (pintype "bidirectional"))
      (node (ref "J4") (pin "8") (pinfunction "8_8") (pintype "bidirectional"))
      (node (ref "U16") (pin "6") (pinfunction "VOUT_6") (pintype "output"))
    )
    (net (code "100") (name "S1") (class "Default")
      (node (ref "J1") (pin "1") (pinfunction "1_1") (pintype "bidirectional"))
      (node (ref "R49") (pin "1") (pinfunction "1_1") (pintype "passive"))
    )
    (net (code "101") (name "S2") (class "Default")
      (node (ref "J1") (pin "3") (pinfunction "3_3") (pintype "bidirectional"))
      (node (ref "R50") (pin "1") (pinfunction "1_1") (pintype "passive"))
    )
    (net (code "102") (name "S3") (class "Default")
      (node (ref "J1") (pin "5") (pinfunction "5_5") (pintype "bidirectional"))
      (node (ref "R51") (pin "1") (pinfunction "1_1") (pintype "passive"))
    )
    (net (code "103") (name "S4") (class "Default")
      (node (ref "J1") (pin "7") (pinfunction "7_7") (pintype "bidirectional"))
      (node (ref "R52") (pin "1") (pinfunction "1_1") (pintype "passive"))
    )
    (net (code "104") (name "S5") (class "Default")
      (node (ref "J2") (pin "1") (pinfunction "1_1") (pintype "bidirectional"))
      (node (ref "R53") (pin "1") (pinfunction "1_1") (pintype "passive"))
    )
    (net (code "105") (name "S6") (class "Default")
      (node (ref "J2") (pin "3") (pinfunction "3_3") (pintype "bidirectional"))
      (node (ref "R54") (pin "1") (pinfunction "1_1") (pintype "passive"))
    )
    (net (code "106") (name "S7") (class "Default")
      (node (ref "J2") (pin "5") (pinfunction "5_5") (pintype "bidirectional"))
      (node (ref "R55") (pin "1") (pinfunction "1_1") (pintype "passive"))
    )
    (net (code "107") (name "S8") (class "Default")
      (node (ref "J2") (pin "7") (pinfunction "7_7") (pintype "bidirectional"))
      (node (ref "R56") (pin "1") (pinfunction "1_1") (pintype "passive"))
    )
    (net (code "108") (name "S9") (class "Default")
      (node (ref "J3") (pin "1") (pinfunction "1_1") (pintype "bidirectional"))
      (node (ref "R58") (pin "1") (pinfunction "1_1") (pintype "passive"))
    )
    (net (code "109") (name "S10") (class "Default")
      (node (ref "J3") (pin "3") (pinfunction "3_3") (pintype "bidirectional"))
      (node (ref "R57") (pin "1") (pinfunction "1_1") (pintype "passive"))
    )
    (net (code "110") (name "S11") (class "Default")
      (node (ref "J3") (pin "5") (pinfunction "5_5") (pintype "bidirectional"))
      (node (ref "R59") (pin "1") (pinfunction "1_1") (pintype "passive"))
    )
    (net (code "111") (name "S12") (class "Default")
      (node (ref "J3") (pin "7") (pinfunction "7_7") (pintype "bidirectional"))
      (node (ref "R60") (pin "1") (pinfunction "1_1") (pintype "passive"))
    )
    (net (code "112") (name "S13") (class "Default")
      (node (ref "J4") (pin "1") (pinfunction "1_1") (pintype "bidirectional"))
      (node (ref "R62") (pin "1") (pinfunction "1_1") (pintype "passive"))
    )
    (net (code "113") (name "S14") (class "Default")
      (node (ref "J4") (pin "3") (pinfunction "3_3") (pintype "bidirectional"))
      (node (ref "R61") (pin "1") (pinfunction "1_1") (pintype "passive"))
    )
    (net (code "114") (name "S15") (class "Default")
      (node (ref "J4") (pin "5") (pinfunction "5_5") (pintype "bidirectional"))
      (node (ref "R64") (pin "1") (pinfunction "1_1") (pintype "passive"))
    )
    (net (code "115") (name "S16") (class "Default")
      (node (ref "J4") (pin "7") (pinfunction "7_7") (pintype "bidirectional"))
      (node (ref "R63") (pin "1") (pinfunction "1_1") (pintype "passive"))
    )
    (net (code "116") (name "unconnected-(U1-DNC-Pad8)") (class "Default")
      (node (ref "U1") (pin "8") (pinfunction "DNC_8") (pintype "passive"))
    )
    (net (code "117") (name "unconnected-(U1-DNC_2-Pad1)") (class "Default")
      (node (ref "U1") (pin "1") (pinfunction "DNC_2_1") (pintype "passive"))
    )
    (net (code "118") (name "unconnected-(U1-NC-Pad7)") (class "Default")
      (node (ref "U1") (pin "7") (pinfunction "NC_7") (pintype "passive"))
    )
    (net (code "119") (name "unconnected-(U1-TEMP-Pad3)") (class "Default")
      (node (ref "U1") (pin "3") (pinfunction "TEMP_3") (pintype "passive"))
    )
    (net (code "120") (name "unconnected-(U1-TRIM{slash}NR-Pad5)") (class "Default")
      (node (ref "U1") (pin "5") (pinfunction "TRIM/NR_5") (pintype "passive"))
    )
    (net (code "121") (name "unconnected-(U2-DNC-Pad8)") (class "Default")
      (node (ref "U2") (pin "8") (pinfunction "DNC_8") (pintype "passive"))
    )
    (net (code "122") (name "unconnected-(U2-DNC_2-Pad1)") (class "Default")
      (node (ref "U2") (pin "1") (pinfunction "DNC_2_1") (pintype "passive"))
    )
    (net (code "123") (name "unconnected-(U2-NC-Pad7)") (class "Default")
      (node (ref "U2") (pin "7") (pinfunction "NC_7") (pintype "passive"))
    )
    (net (code "124") (name "unconnected-(U2-TEMP-Pad3)") (class "Default")
      (node (ref "U2") (pin "3") (pinfunction "TEMP_3") (pintype "passive"))
    )
    (net (code "125") (name "unconnected-(U2-TRIM{slash}NR-Pad5)") (class "Default")
      (node (ref "U2") (pin "5") (pinfunction "TRIM/NR_5") (pintype "passive"))
    )
    (net (code "126") (name "unconnected-(U3-DNC-Pad8)") (class "Default")
      (node (ref "U3") (pin "8") (pinfunction "DNC_8") (pintype "passive"))
    )
    (net (code "127") (name "unconnected-(U3-DNC_2-Pad1)") (class "Default")
      (node (ref "U3") (pin "1") (pinfunction "DNC_2_1") (pintype "passive"))
    )
    (net (code "128") (name "unconnected-(U3-NC-Pad7)") (class "Default")
      (node (ref "U3") (pin "7") (pinfunction "NC_7") (pintype "passive"))
    )
    (net (code "129") (name "unconnected-(U3-TEMP-Pad3)") (class "Default")
      (node (ref "U3") (pin "3") (pinfunction "TEMP_3") (pintype "passive"))
    )
    (net (code "130") (name "unconnected-(U3-TRIM{slash}NR-Pad5)") (class "Default")
      (node (ref "U3") (pin "5") (pinfunction "TRIM/NR_5") (pintype "passive"))
    )
    (net (code "131") (name "unconnected-(U4-DNC-Pad8)") (class "Default")
      (node (ref "U4") (pin "8") (pinfunction "DNC_8") (pintype "passive"))
    )
    (net (code "132") (name "unconnected-(U4-DNC_2-Pad1)") (class "Default")
      (node (ref "U4") (pin "1") (pinfunction "DNC_2_1") (pintype "passive"))
    )
    (net (code "133") (name "unconnected-(U4-NC-Pad7)") (class "Default")
      (node (ref "U4") (pin "7") (pinfunction "NC_7") (pintype "passive"))
    )
    (net (code "134") (name "unconnected-(U4-TEMP-Pad3)") (class "Default")
      (node (ref "U4") (pin "3") (pinfunction "TEMP_3") (pintype "passive"))
    )
    (net (code "135") (name "unconnected-(U4-TRIM{slash}NR-Pad5)") (class "Default")
      (node (ref "U4") (pin "5") (pinfunction "TRIM/NR_5") (pintype "passive"))
    )
    (net (code "136") (name "unconnected-(U5-DNC-Pad8)") (class "Default")
      (node (ref "U5") (pin "8") (pinfunction "DNC_8") (pintype "passive"))
    )
    (net (code "137") (name "unconnected-(U5-DNC_2-Pad1)") (class "Default")
      (node (ref "U5") (pin "1") (pinfunction "DNC_2_1") (pintype "passive"))
    )
    (net (code "138") (name "unconnected-(U5-NC-Pad7)") (class "Default")
      (node (ref "U5") (pin "7") (pinfunction "NC_7") (pintype "passive"))
    )
    (net (code "139") (name "unconnected-(U5-TEMP-Pad3)") (class "Default")
      (node (ref "U5") (pin "3") (pinfunction "TEMP_3") (pintype "passive"))
    )
    (net (code "140") (name "unconnected-(U5-TRIM{slash}NR-Pad5)") (class "Default")
      (node (ref "U5") (pin "5") (pinfunction "TRIM/NR_5") (pintype "passive"))
    )
    (net (code "141") (name "unconnected-(U6-DNC-Pad8)") (class "Default")
      (node (ref "U6") (pin "8") (pinfunction "DNC_8") (pintype "passive"))
    )
    (net (code "142") (name "unconnected-(U6-DNC_2-Pad1)") (class "Default")
      (node (ref "U6") (pin "1") (pinfunction "DNC_2_1") (pintype "passive"))
    )
    (net (code "143") (name "unconnected-(U6-NC-Pad7)") (class "Default")
      (node (ref "U6") (pin "7") (pinfunction "NC_7") (pintype "passive"))
    )
    (net (code "144") (name "unconnected-(U6-TEMP-Pad3)") (class "Default")
      (node (ref "U6") (pin "3") (pinfunction "TEMP_3") (pintype "passive"))
    )
    (net (code "145") (name "unconnected-(U6-TRIM{slash}NR-Pad5)") (class "Default")
      (node (ref "U6") (pin "5") (pinfunction "TRIM/NR_5") (pintype "passive"))
    )
    (net (code "146") (name "unconnected-(U7-DNC-Pad8)") (class "Default")
      (node (ref "U7") (pin "8") (pinfunction "DNC_8") (pintype "passive"))
    )
    (net (code "147") (name "unconnected-(U7-DNC_2-Pad1)") (class "Default")
      (node (ref "U7") (pin "1") (pinfunction "DNC_2_1") (pintype "passive"))
    )
    (net (code "148") (name "unconnected-(U7-NC-Pad7)") (class "Default")
      (node (ref "U7") (pin "7") (pinfunction "NC_7") (pintype "passive"))
    )
    (net (code "149") (name "unconnected-(U7-TEMP-Pad3)") (class "Default")
      (node (ref "U7") (pin "3") (pinfunction "TEMP_3") (pintype "passive"))
    )
    (net (code "150") (name "unconnected-(U7-TRIM{slash}NR-Pad5)") (class "Default")
      (node (ref "U7") (pin "5") (pinfunction "TRIM/NR_5") (pintype "passive"))
    )
    (net (code "151") (name "unconnected-(U8-DNC-Pad8)") (class "Default")
      (node (ref "U8") (pin "8") (pinfunction "DNC_8") (pintype "passive"))
    )
    (net (code "152") (name "unconnected-(U8-DNC_2-Pad1)") (class "Default")
      (node (ref "U8") (pin "1") (pinfunction "DNC_2_1") (pintype "passive"))
    )
    (net (code "153") (name "unconnected-(U8-NC-Pad7)") (class "Default")
      (node (ref "U8") (pin "7") (pinfunction "NC_7") (pintype "passive"))
    )
    (net (code "154") (name "unconnected-(U8-TEMP-Pad3)") (class "Default")
      (node (ref "U8") (pin "3") (pinfunction "TEMP_3") (pintype "passive"))
    )
    (net (code "155") (name "unconnected-(U8-TRIM{slash}NR-Pad5)") (class "Default")
      (node (ref "U8") (pin "5") (pinfunction "TRIM/NR_5") (pintype "passive"))
    )
    (net (code "156") (name "unconnected-(U9-DNC-Pad8)") (class "Default")
      (node (ref "U9") (pin "8") (pinfunction "DNC_8") (pintype "passive"))
    )
    (net (code "157") (name "unconnected-(U9-DNC_2-Pad1)") (class "Default")
      (node (ref "U9") (pin "1") (pinfunction "DNC_2_1") (pintype "passive"))
    )
    (net (code "158") (name "unconnected-(U9-NC-Pad7)") (class "Default")
      (node (ref "U9") (pin "7") (pinfunction "NC_7") (pintype "passive"))
    )
    (net (code "159") (name "unconnected-(U9-TEMP-Pad3)") (class "Default")
      (node (ref "U9") (pin "3") (pinfunction "TEMP_3") (pintype "passive"))
    )
    (net (code "160") (name "unconnected-(U9-TRIM{slash}NR-Pad5)") (class "Default")
      (node (ref "U9") (pin "5") (pinfunction "TRIM/NR_5") (pintype "passive"))
    )
    (net (code "161") (name "unconnected-(U10-DNC-Pad8)") (class "Default")
      (node (ref "U10") (pin "8") (pinfunction "DNC_8") (pintype "passive"))
    )
    (net (code "162") (name "unconnected-(U10-DNC_2-Pad1)") (class "Default")
      (node (ref "U10") (pin "1") (pinfunction "DNC_2_1") (pintype "passive"))
    )
    (net (code "163") (name "unconnected-(U10-NC-Pad7)") (class "Default")
      (node (ref "U10") (pin "7") (pinfunction "NC_7") (pintype "passive"))
    )
    (net (code "164") (name "unconnected-(U10-TEMP-Pad3)") (class "Default")
      (node (ref "U10") (pin "3") (pinfunction "TEMP_3") (pintype "passive"))
    )
    (net (code "165") (name "unconnected-(U10-TRIM{slash}NR-Pad5)") (class "Default")
      (node (ref "U10") (pin "5") (pinfunction "TRIM/NR_5") (pintype "passive"))
    )
    (net (code "166") (name "unconnected-(U11-DNC-Pad8)") (class "Default")
      (node (ref "U11") (pin "8") (pinfunction "DNC_8") (pintype "passive"))
    )
    (net (code "167") (name "unconnected-(U11-DNC_2-Pad1)") (class "Default")
      (node (ref "U11") (pin "1") (pinfunction "DNC_2_1") (pintype "passive"))
    )
    (net (code "168") (name "unconnected-(U11-NC-Pad7)") (class "Default")
      (node (ref "U11") (pin "7") (pinfunction "NC_7") (pintype "passive"))
    )
    (net (code "169") (name "unconnected-(U11-TEMP-Pad3)") (class "Default")
      (node (ref "U11") (pin "3") (pinfunction "TEMP_3") (pintype "passive"))
    )
    (net (code "170") (name "unconnected-(U11-TRIM{slash}NR-Pad5)") (class "Default")
      (node (ref "U11") (pin "5") (pinfunction "TRIM/NR_5") (pintype "passive"))
    )
    (net (code "171") (name "unconnected-(U12-DNC-Pad8)") (class "Default")
      (node (ref "U12") (pin "8") (pinfunction "DNC_8") (pintype "passive"))
    )
    (net (code "172") (name "unconnected-(U12-DNC_2-Pad1)") (class "Default")
      (node (ref "U12") (pin "1") (pinfunction "DNC_2_1") (pintype "passive"))
    )
    (net (code "173") (name "unconnected-(U12-NC-Pad7)") (class "Default")
      (node (ref "U12") (pin "7") (pinfunction "NC_7") (pintype "passive"))
    )
    (net (code "174") (name "unconnected-(U12-TEMP-Pad3)") (class "Default")
      (node (ref "U12") (pin "3") (pinfunction "TEMP_3") (pintype "passive"))
    )
    (net (code "175") (name "unconnected-(U12-TRIM{slash}NR-Pad5)") (class "Default")
      (node (ref "U12") (pin "5") (pinfunction "TRIM/NR_5") (pintype "passive"))
    )
    (net (code "176") (name "unconnected-(U13-DNC-Pad8)") (class "Default")
      (node (ref "U13") (pin "8") (pinfunction "DNC_8") (pintype "passive"))
    )
    (net (code "177") (name "unconnected-(U13-DNC_2-Pad1)") (class "Default")
      (node (ref "U13") (pin "1") (pinfunction "DNC_2_1") (pintype "passive"))
    )
    (net (code "178") (name "unconnected-(U13-NC-Pad7)") (class "Default")
      (node (ref "U13") (pin "7") (pinfunction "NC_7") (pintype "passive"))
    )
    (net (code "179") (name "unconnected-(U13-TEMP-Pad3)") (class "Default")
      (node (ref "U13") (pin "3") (pinfunction "TEMP_3") (pintype "passive"))
    )
    (net (code "180") (name "unconnected-(U13-TRIM{slash}NR-Pad5)") (class "Default")
      (node (ref "U13") (pin "5") (pinfunction "TRIM/NR_5") (pintype "passive"))
    )
    (net (code "181") (name "unconnected-(U14-DNC-Pad8)") (class "Default")
      (node (ref "U14") (pin "8") (pinfunction "DNC_8") (pintype "passive"))
    )
    (net (code "182") (name "unconnected-(U14-DNC_2-Pad1)") (class "Default")
      (node (ref "U14") (pin "1") (pinfunction "DNC_2_1") (pintype "passive"))
    )
    (net (code "183") (name "unconnected-(U14-NC-Pad7)") (class "Default")
      (node (ref "U14") (pin "7") (pinfunction "NC_7") (pintype "passive"))
    )
    (net (code "184") (name "unconnected-(U14-TEMP-Pad3)") (class "Default")
      (node (ref "U14") (pin "3") (pinfunction "TEMP_3") (pintype "passive"))
    )
    (net (code "185") (name "unconnected-(U14-TRIM{slash}NR-Pad5)") (class "Default")
      (node (ref "U14") (pin "5") (pinfunction "TRIM/NR_5") (pintype "passive"))
    )
    (net (code "186") (name "unconnected-(U15-DNC-Pad8)") (class "Default")
      (node (ref "U15") (pin "8") (pinfunction "DNC_8") (pintype "passive"))
    )
    (net (code "187") (name "unconnected-(U15-DNC_2-Pad1)") (class "Default")
      (node (ref "U15") (pin "1") (pinfunction "DNC_2_1") (pintype "passive"))
    )
    (net (code "188") (name "unconnected-(U15-NC-Pad7)") (class "Default")
      (node (ref "U15") (pin "7") (pinfunction "NC_7") (pintype "passive"))
    )
    (net (code "189") (name "unconnected-(U15-TEMP-Pad3)") (class "Default")
      (node (ref "U15") (pin "3") (pinfunction "TEMP_3") (pintype "passive"))
    )
    (net (code "190") (name "unconnected-(U15-TRIM{slash}NR-Pad5)") (class "Default")
      (node (ref "U15") (pin "5") (pinfunction "TRIM/NR_5") (pintype "passive"))
    )
    (net (code "191") (name "unconnected-(U16-DNC-Pad8)") (class "Default")
      (node (ref "U16") (pin "8") (pinfunction "DNC_8") (pintype "passive"))
    )
    (net (code "192") (name "unconnected-(U16-DNC_2-Pad1)") (class "Default")
      (node (ref "U16") (pin "1") (pinfunction "DNC_2_1") (pintype "passive"))
    )
    (net (code "193") (name "unconnected-(U16-NC-Pad7)") (class "Default")
      (node (ref "U16") (pin "7") (pinfunction "NC_7") (pintype "passive"))
    )
    (net (code "194") (name "unconnected-(U16-TEMP-Pad3)") (class "Default")
      (node (ref "U16") (pin "3") (pinfunction "TEMP_3") (pintype "passive"))
    )
    (net (code "195") (name "unconnected-(U16-TRIM{slash}NR-Pad5)") (class "Default")
      (node (ref "U16") (pin "5") (pinfunction "TRIM/NR_5") (pintype "passive"))
    )
  )
)
